# lockdriver.net
KiCad netlist of a schematic drawn in Altium Designer
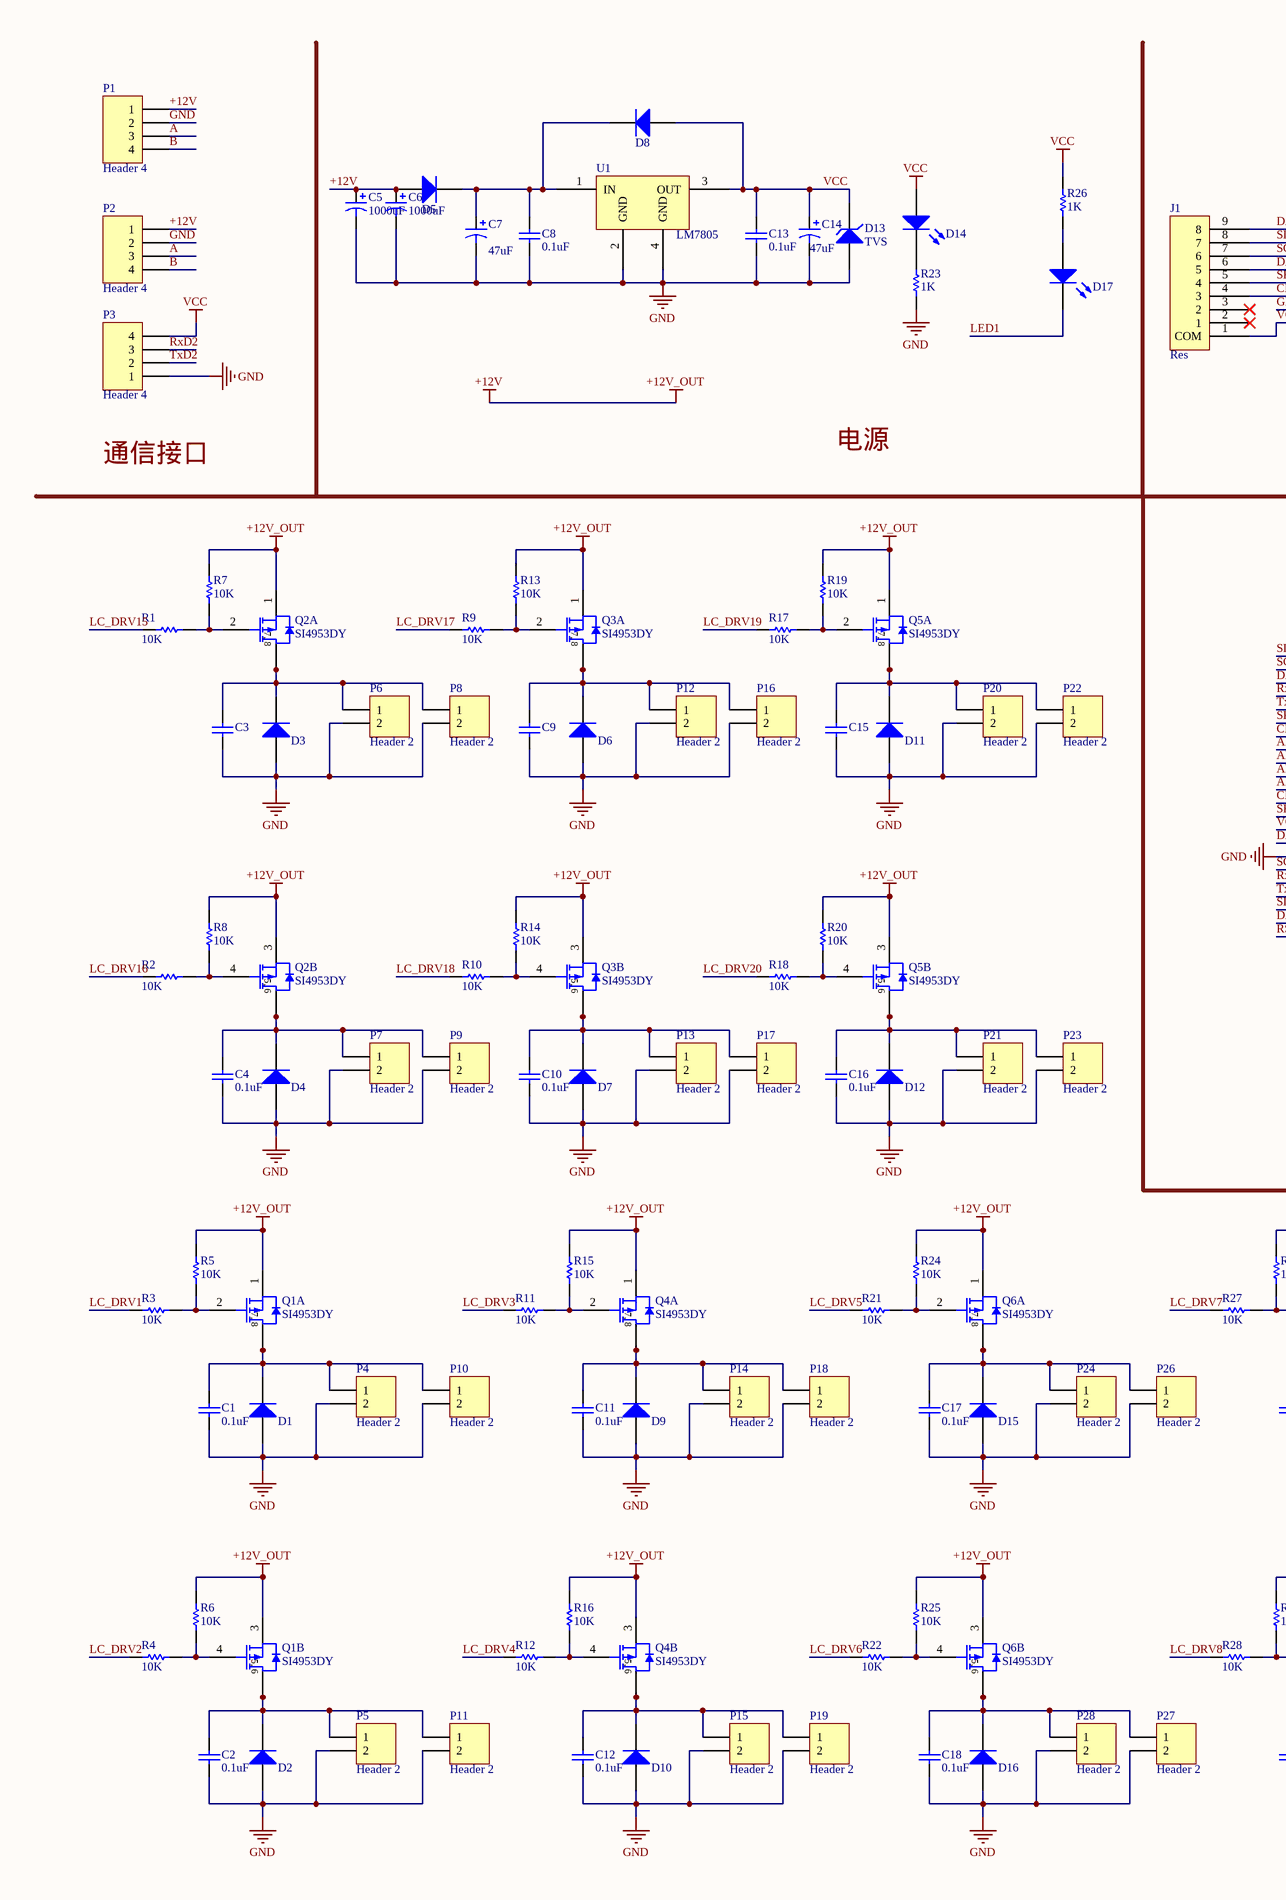
[diagram p0: lockdriver.SchDoc, left]
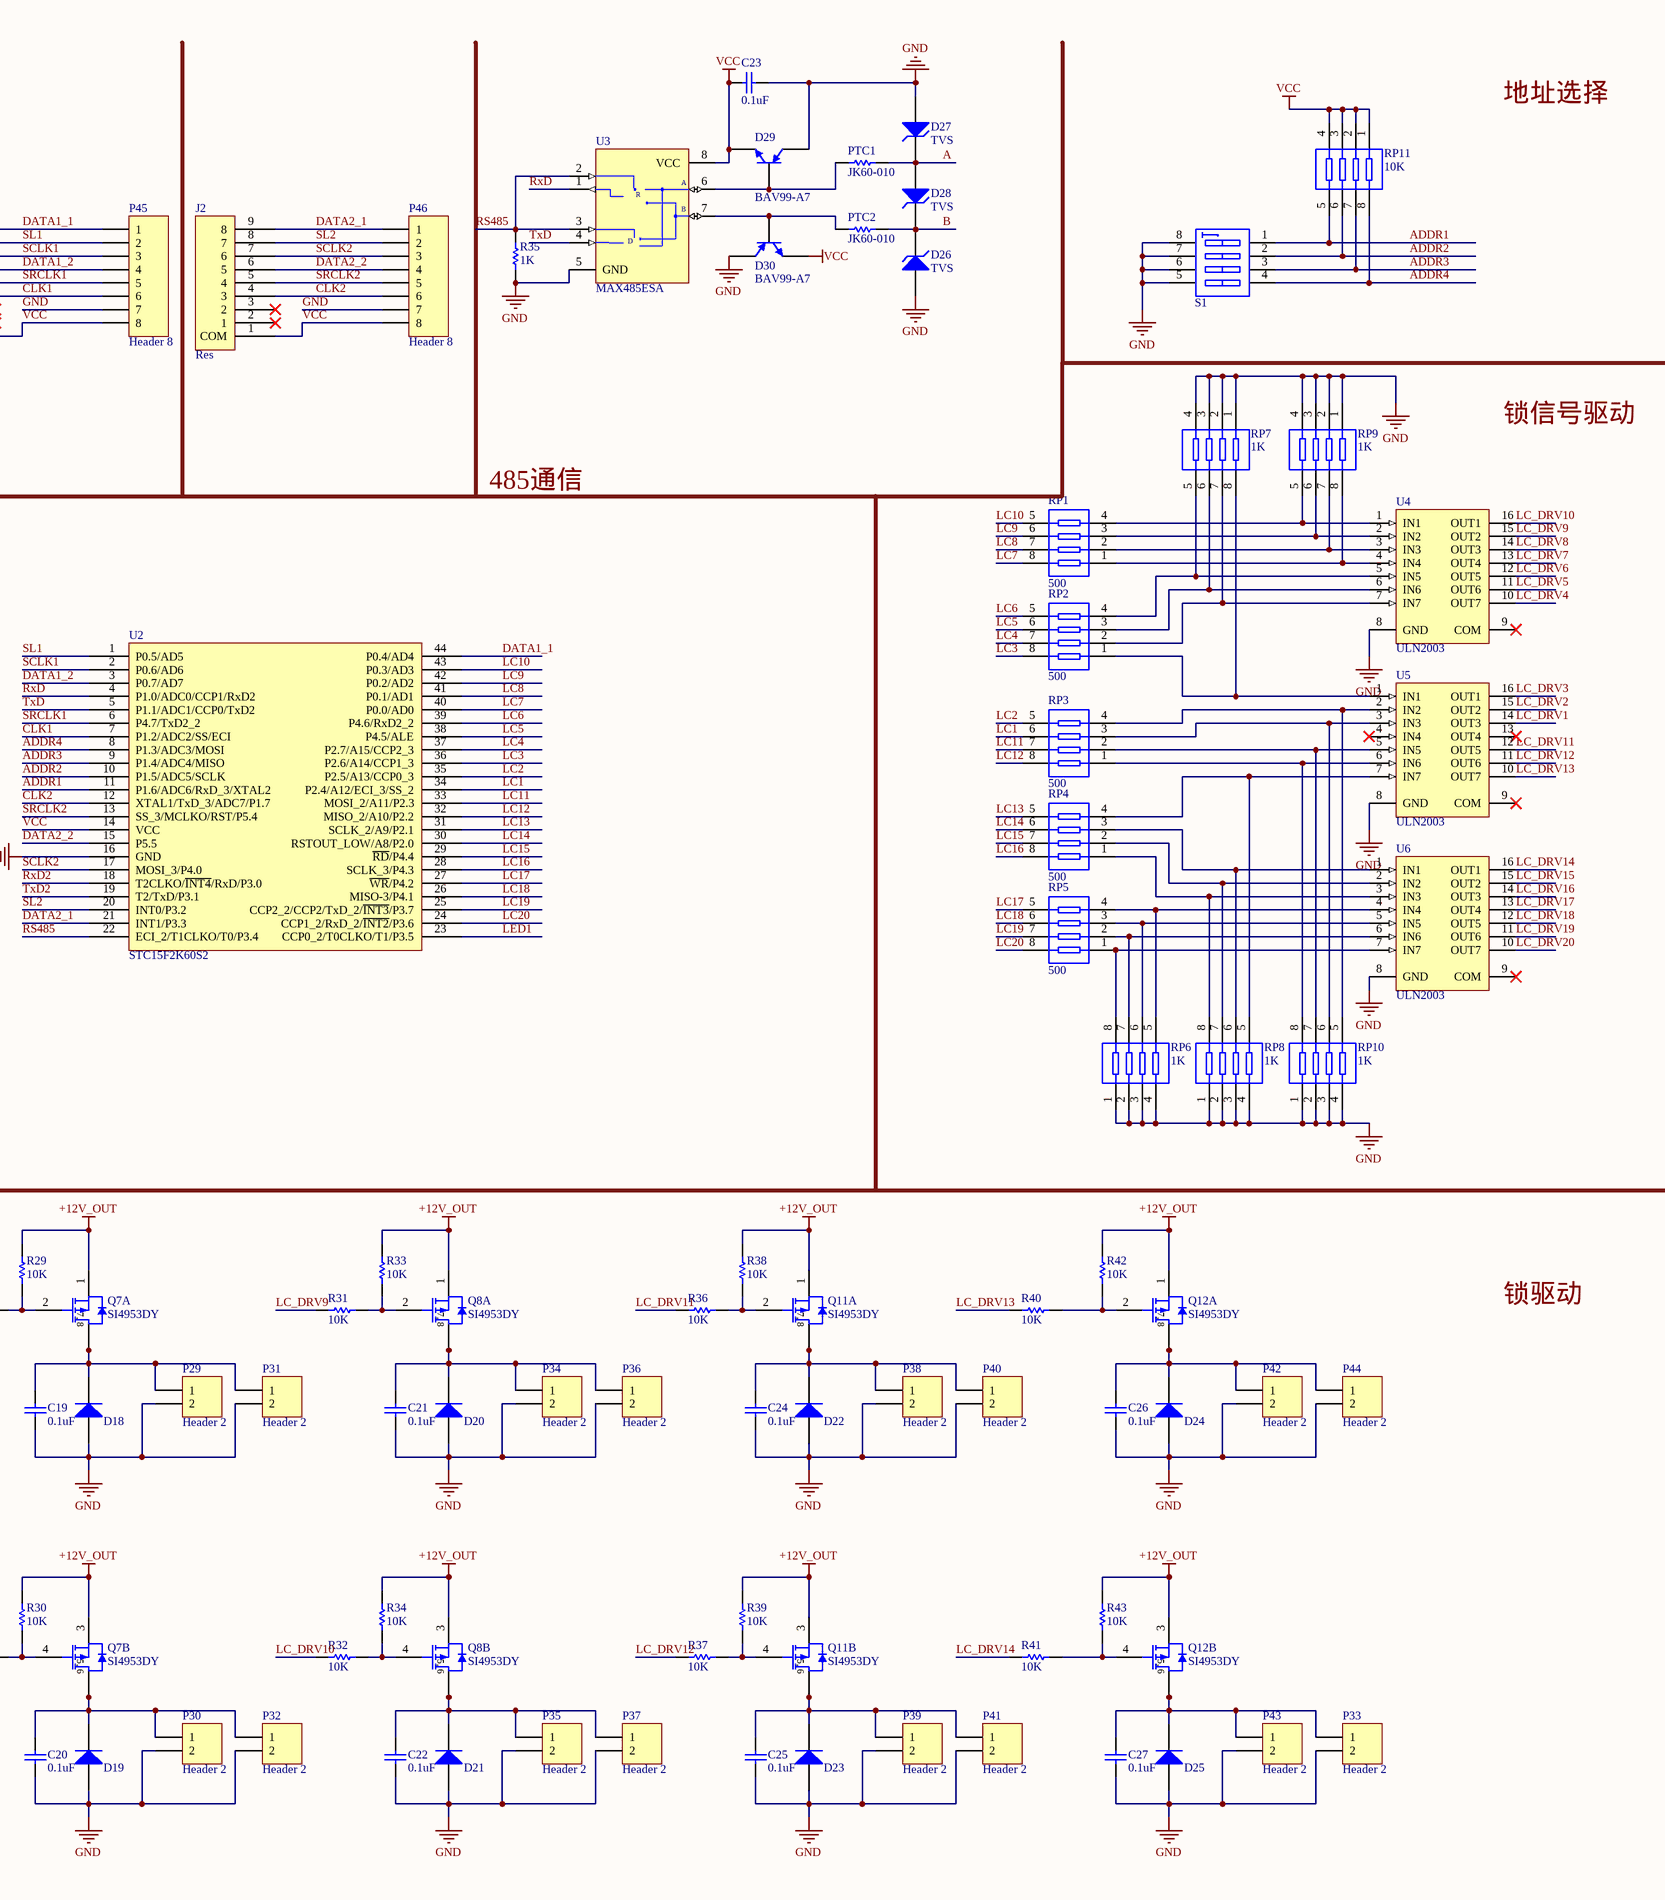
[diagram p1: lockdriver.SchDoc, right]

(export (version "E")
  (design (tool "Eeschema 10.0.6"))
  (components
    (comp (ref "C1")
      (value "0.1uF")
      (footprint "CAPC2012M")
      (description "Capacitor")
      (fields (field (name "PUBLISHER") "Altium Limited"))
      (libsource (lib "device") (part "Cap"))
    )
    (comp (ref "C2")
      (value "0.1uF")
      (footprint "CAPC2012M")
      (description "Capacitor")
      (fields (field (name "PUBLISHER") "Altium Limited"))
      (libsource (lib "device") (part "Cap"))
    )
    (comp (ref "C3")
      (value "0.1uF")
      (footprint "CAPC2012M")
      (description "Capacitor")
      (fields (field (name "PUBLISHER") "Altium Limited"))
      (libsource (lib "device") (part "Cap"))
    )
    (comp (ref "C4")
      (value "0.1uF")
      (footprint "CAPC2012M")
      (description "Capacitor")
      (fields (field (name "PUBLISHER") "Altium Limited"))
      (libsource (lib "device") (part "Cap"))
    )
    (comp (ref "C5")
      (value "1000uF")
      (footprint "CAPPR5-10x12.5")
      (description "Polarized Capacitor (1000uf)")
      (fields (field (name "PUBLISHER") "Altium Limited"))
      (libsource (lib "device") (part "Cap Pol4"))
    )
    (comp (ref "C6")
      (value "1000uF")
      (footprint "CAPPR5-10x12.5")
      (description "Polarized Capacitor (1000uf)")
      (fields (field (name "PUBLISHER") "Altium Limited"))
      (libsource (lib "device") (part "Cap Pol4"))
    )
    (comp (ref "C7")
      (value "47uF")
      (footprint "CAPPR2-5x11.5")
      (description "Polarized Capacitor (22uf-47uf)")
      (fields (field (name "Comment") "Cap Pol2") (field (name "PUBLISHER") "Altium Limited"))
      (libsource (lib "device") (part "Cap Pol2"))
    )
    (comp (ref "C8")
      (value "0.1uF")
      (footprint "CAPC2012M")
      (description "Capacitor")
      (fields (field (name "PUBLISHER") "Altium Limited"))
      (libsource (lib "device") (part "Cap"))
    )
    (comp (ref "C9")
      (value "0.1uF")
      (footprint "CAPC2012M")
      (description "Capacitor")
      (fields (field (name "PUBLISHER") "Altium Limited"))
      (libsource (lib "device") (part "Cap"))
    )
    (comp (ref "C10")
      (value "0.1uF")
      (footprint "CAPC2012M")
      (description "Capacitor")
      (fields (field (name "PUBLISHER") "Altium Limited"))
      (libsource (lib "device") (part "Cap"))
    )
    (comp (ref "C11")
      (value "0.1uF")
      (footprint "CAPC2012M")
      (description "Capacitor")
      (fields (field (name "PUBLISHER") "Altium Limited"))
      (libsource (lib "device") (part "Cap"))
    )
    (comp (ref "C12")
      (value "0.1uF")
      (footprint "CAPC2012M")
      (description "Capacitor")
      (fields (field (name "PUBLISHER") "Altium Limited"))
      (libsource (lib "device") (part "Cap"))
    )
    (comp (ref "C13")
      (value "0.1uF")
      (footprint "CAPC2012M")
      (description "Capacitor")
      (fields (field (name "PUBLISHER") "Altium Limited"))
      (libsource (lib "device") (part "Cap"))
    )
    (comp (ref "C14")
      (value "47uF")
      (footprint "CAPPR2-5x11.5")
      (description "Polarized Capacitor (22uf-47uf)")
      (fields (field (name "Comment") "Cap Pol2") (field (name "PUBLISHER") "Altium Limited"))
      (libsource (lib "device") (part "Cap Pol2"))
    )
    (comp (ref "C15")
      (value "0.1uF")
      (footprint "CAPC2012M")
      (description "Capacitor")
      (fields (field (name "PUBLISHER") "Altium Limited"))
      (libsource (lib "device") (part "Cap"))
    )
    (comp (ref "C16")
      (value "0.1uF")
      (footprint "CAPC2012M")
      (description "Capacitor")
      (fields (field (name "PUBLISHER") "Altium Limited"))
      (libsource (lib "device") (part "Cap"))
    )
    (comp (ref "C17")
      (value "0.1uF")
      (footprint "CAPC2012M")
      (description "Capacitor")
      (fields (field (name "PUBLISHER") "Altium Limited"))
      (libsource (lib "device") (part "Cap"))
    )
    (comp (ref "C18")
      (value "0.1uF")
      (footprint "CAPC2012M")
      (description "Capacitor")
      (fields (field (name "PUBLISHER") "Altium Limited"))
      (libsource (lib "device") (part "Cap"))
    )
    (comp (ref "C19")
      (value "0.1uF")
      (footprint "CAPC2012M")
      (description "Capacitor")
      (fields (field (name "PUBLISHER") "Altium Limited"))
      (libsource (lib "device") (part "Cap"))
    )
    (comp (ref "C20")
      (value "0.1uF")
      (footprint "CAPC2012M")
      (description "Capacitor")
      (fields (field (name "PUBLISHER") "Altium Limited"))
      (libsource (lib "device") (part "Cap"))
    )
    (comp (ref "C21")
      (value "0.1uF")
      (footprint "CAPC2012M")
      (description "Capacitor")
      (fields (field (name "PUBLISHER") "Altium Limited"))
      (libsource (lib "device") (part "Cap"))
    )
    (comp (ref "C22")
      (value "0.1uF")
      (footprint "CAPC2012M")
      (description "Capacitor")
      (fields (field (name "PUBLISHER") "Altium Limited"))
      (libsource (lib "device") (part "Cap"))
    )
    (comp (ref "C23")
      (value "0.1uF")
      (footprint "CAPC2012M")
      (description "Capacitor")
      (fields (field (name "PUBLISHER") "Altium Limited"))
      (libsource (lib "device") (part "Cap"))
    )
    (comp (ref "C24")
      (value "0.1uF")
      (footprint "CAPC2012M")
      (description "Capacitor")
      (fields (field (name "PUBLISHER") "Altium Limited"))
      (libsource (lib "device") (part "Cap"))
    )
    (comp (ref "C25")
      (value "0.1uF")
      (footprint "CAPC2012M")
      (description "Capacitor")
      (fields (field (name "PUBLISHER") "Altium Limited"))
      (libsource (lib "device") (part "Cap"))
    )
    (comp (ref "C26")
      (value "0.1uF")
      (footprint "CAPC2012M")
      (description "Capacitor")
      (fields (field (name "PUBLISHER") "Altium Limited"))
      (libsource (lib "device") (part "Cap"))
    )
    (comp (ref "C27")
      (value "0.1uF")
      (footprint "CAPC2012M")
      (description "Capacitor")
      (fields (field (name "PUBLISHER") "Altium Limited"))
      (libsource (lib "device") (part "Cap"))
    )
    (comp (ref "D1")
      (value "1N4007")
      (footprint "DSO-C2/X1.8")
      (description "Default Diode")
      (fields (field (name "PUBLISHER") "Altium Limited"))
      (libsource (lib "device") (part "Diode"))
    )
    (comp (ref "D2")
      (value "1N4007")
      (footprint "DSO-C2/X1.8")
      (description "Default Diode")
      (fields (field (name "PUBLISHER") "Altium Limited"))
      (libsource (lib "device") (part "Diode"))
    )
    (comp (ref "D3")
      (value "1N4007")
      (footprint "DSO-C2/X1.8")
      (description "Default Diode")
      (fields (field (name "PUBLISHER") "Altium Limited"))
      (libsource (lib "device") (part "Diode"))
    )
    (comp (ref "D4")
      (value "1N4007")
      (footprint "DSO-C2/X1.8")
      (description "Default Diode")
      (fields (field (name "PUBLISHER") "Altium Limited"))
      (libsource (lib "device") (part "Diode"))
    )
    (comp (ref "D5")
      (value "1N4007")
      (footprint "DSO-C2/X1.8")
      (description "Default Diode")
      (fields (field (name "PUBLISHER") "Altium Limited"))
      (libsource (lib "device") (part "Diode"))
    )
    (comp (ref "D6")
      (value "1N4007")
      (footprint "DSO-C2/X1.8")
      (description "Default Diode")
      (fields (field (name "PUBLISHER") "Altium Limited"))
      (libsource (lib "device") (part "Diode"))
    )
    (comp (ref "D7")
      (value "1N4007")
      (footprint "DSO-C2/X1.8")
      (description "Default Diode")
      (fields (field (name "PUBLISHER") "Altium Limited"))
      (libsource (lib "device") (part "Diode"))
    )
    (comp (ref "D8")
      (value "1N4007")
      (footprint "DSO-C2/X1.8")
      (description "Default Diode")
      (fields (field (name "PUBLISHER") "Altium Limited"))
      (libsource (lib "device") (part "Diode"))
    )
    (comp (ref "D9")
      (value "1N4007")
      (footprint "DSO-C2/X1.8")
      (description "Default Diode")
      (fields (field (name "PUBLISHER") "Altium Limited"))
      (libsource (lib "device") (part "Diode"))
    )
    (comp (ref "D10")
      (value "1N4007")
      (footprint "DSO-C2/X1.8")
      (description "Default Diode")
      (fields (field (name "PUBLISHER") "Altium Limited"))
      (libsource (lib "device") (part "Diode"))
    )
    (comp (ref "D11")
      (value "1N4007")
      (footprint "DSO-C2/X1.8")
      (description "Default Diode")
      (fields (field (name "PUBLISHER") "Altium Limited"))
      (libsource (lib "device") (part "Diode"))
    )
    (comp (ref "D12")
      (value "1N4007")
      (footprint "DSO-C2/X1.8")
      (description "Default Diode")
      (fields (field (name "PUBLISHER") "Altium Limited"))
      (libsource (lib "device") (part "Diode"))
    )
    (comp (ref "D13")
      (value "TVS")
      (footprint "DSO-C2/X1.8")
      (description "TVS瞬态抑制二极管")
      (fields (field (name "PUBLISHER") "Altium Limited"))
      (libsource (lib "device") (part "TVS"))
    )
    (comp (ref "D14")
      (value "LED")
      (footprint "LED2012M")
      (description "Typical INFRARED GaAs LED")
      (fields (field (name "PUBLISHER") "Altium Limited"))
      (libsource (lib "device") (part "LED"))
    )
    (comp (ref "D15")
      (value "1N4007")
      (footprint "DSO-C2/X1.8")
      (description "Default Diode")
      (fields (field (name "PUBLISHER") "Altium Limited"))
      (libsource (lib "device") (part "Diode"))
    )
    (comp (ref "D16")
      (value "1N4007")
      (footprint "DSO-C2/X1.8")
      (description "Default Diode")
      (fields (field (name "PUBLISHER") "Altium Limited"))
      (libsource (lib "device") (part "Diode"))
    )
    (comp (ref "D17")
      (value "LED")
      (footprint "LED2012M")
      (description "Typical INFRARED GaAs LED")
      (fields (field (name "PUBLISHER") "Altium Limited"))
      (libsource (lib "device") (part "LED"))
    )
    (comp (ref "D18")
      (value "1N4007")
      (footprint "DSO-C2/X1.8")
      (description "Default Diode")
      (fields (field (name "PUBLISHER") "Altium Limited"))
      (libsource (lib "device") (part "Diode"))
    )
    (comp (ref "D19")
      (value "1N4007")
      (footprint "DSO-C2/X1.8")
      (description "Default Diode")
      (fields (field (name "PUBLISHER") "Altium Limited"))
      (libsource (lib "device") (part "Diode"))
    )
    (comp (ref "D20")
      (value "1N4007")
      (footprint "DSO-C2/X1.8")
      (description "Default Diode")
      (fields (field (name "PUBLISHER") "Altium Limited"))
      (libsource (lib "device") (part "Diode"))
    )
    (comp (ref "D21")
      (value "1N4007")
      (footprint "DSO-C2/X1.8")
      (description "Default Diode")
      (fields (field (name "PUBLISHER") "Altium Limited"))
      (libsource (lib "device") (part "Diode"))
    )
    (comp (ref "D22")
      (value "1N4007")
      (footprint "DSO-C2/X1.8")
      (description "Default Diode")
      (fields (field (name "PUBLISHER") "Altium Limited"))
      (libsource (lib "device") (part "Diode"))
    )
    (comp (ref "D23")
      (value "1N4007")
      (footprint "DSO-C2/X1.8")
      (description "Default Diode")
      (fields (field (name "PUBLISHER") "Altium Limited"))
      (libsource (lib "device") (part "Diode"))
    )
    (comp (ref "D24")
      (value "1N4007")
      (footprint "DSO-C2/X1.8")
      (description "Default Diode")
      (fields (field (name "PUBLISHER") "Altium Limited"))
      (libsource (lib "device") (part "Diode"))
    )
    (comp (ref "D25")
      (value "1N4007")
      (footprint "DSO-C2/X1.8")
      (description "Default Diode")
      (fields (field (name "PUBLISHER") "Altium Limited"))
      (libsource (lib "device") (part "Diode"))
    )
    (comp (ref "D26")
      (value "TVS")
      (footprint "DSO-C2/X1.8")
      (description "TVS瞬态抑制二极管")
      (fields (field (name "PUBLISHER") "Altium Limited"))
      (libsource (lib "device") (part "TVS"))
    )
    (comp (ref "D27")
      (value "TVS")
      (footprint "DSO-C2/X1.8")
      (description "TVS瞬态抑制二极管")
      (fields (field (name "PUBLISHER") "Altium Limited"))
      (libsource (lib "device") (part "TVS"))
    )
    (comp (ref "D28")
      (value "TVS")
      (footprint "DSO-C2/X1.8")
      (description "TVS瞬态抑制二极管")
      (fields (field (name "PUBLISHER") "Altium Limited"))
      (libsource (lib "device") (part "TVS"))
    )
    (comp (ref "D29") (value "BAV99-A7") (footprint "SOT23-3M") (libsource (lib "device") (part "BAV99-A7")))
    (comp (ref "D30") (value "BAV99-A7") (footprint "SOT23-3M") (libsource (lib "device") (part "BAV99-A7")))
    (comp (ref "J1") (value "Res") (footprint "SIP9") (libsource (lib "device") (part "Res Pack2")))
    (comp (ref "J2") (value "Res") (footprint "SIP9") (libsource (lib "device") (part "Res Pack2")))
    (comp (ref "P1")
      (value "Header 4")
      (footprint "VH396-4")
      (description "Header, 4-Pin")
      (fields (field (name "PUBLISHER") "Altium Limited"))
      (libsource (lib "connector") (part "Header 4"))
    )
    (comp (ref "P2")
      (value "Header 4")
      (footprint "VH396-4")
      (description "Header, 4-Pin")
      (fields (field (name "PUBLISHER") "Altium Limited"))
      (libsource (lib "connector") (part "Header 4"))
    )
    (comp (ref "P3")
      (value "Header 4")
      (footprint "HDR1X4")
      (description "Header, 4-Pin")
      (fields (field (name "PUBLISHER") "Altium Limited"))
      (libsource (lib "") (part "Header 4_1"))
    )
    (comp (ref "P4")
      (value "Header 2")
      (footprint "VH396-2")
      (description "Header, 2-Pin")
      (fields (field (name "PUBLISHER") "Altium Limited"))
      (libsource (lib "connector") (part "Header 2"))
    )
    (comp (ref "P5")
      (value "Header 2")
      (footprint "VH396-2")
      (description "Header, 2-Pin")
      (fields (field (name "PUBLISHER") "Altium Limited"))
      (libsource (lib "connector") (part "Header 2"))
    )
    (comp (ref "P6")
      (value "Header 2")
      (footprint "VH396-2")
      (description "Header, 2-Pin")
      (fields (field (name "PUBLISHER") "Altium Limited"))
      (libsource (lib "connector") (part "Header 2"))
    )
    (comp (ref "P7")
      (value "Header 2")
      (footprint "VH396-2")
      (description "Header, 2-Pin")
      (fields (field (name "PUBLISHER") "Altium Limited"))
      (libsource (lib "connector") (part "Header 2"))
    )
    (comp (ref "P8")
      (value "Header 2")
      (footprint "XH254-2")
      (description "Header, 2-Pin")
      (fields (field (name "PUBLISHER") "Altium Limited"))
      (libsource (lib "connector") (part "Header 2"))
    )
    (comp (ref "P9")
      (value "Header 2")
      (footprint "XH254-2")
      (description "Header, 2-Pin")
      (fields (field (name "PUBLISHER") "Altium Limited"))
      (libsource (lib "connector") (part "Header 2"))
    )
    (comp (ref "P10")
      (value "Header 2")
      (footprint "XH254-2")
      (description "Header, 2-Pin")
      (fields (field (name "PUBLISHER") "Altium Limited"))
      (libsource (lib "connector") (part "Header 2"))
    )
    (comp (ref "P11")
      (value "Header 2")
      (footprint "XH254-2")
      (description "Header, 2-Pin")
      (fields (field (name "PUBLISHER") "Altium Limited"))
      (libsource (lib "connector") (part "Header 2"))
    )
    (comp (ref "P12")
      (value "Header 2")
      (footprint "VH396-2")
      (description "Header, 2-Pin")
      (fields (field (name "PUBLISHER") "Altium Limited"))
      (libsource (lib "connector") (part "Header 2"))
    )
    (comp (ref "P13")
      (value "Header 2")
      (footprint "VH396-2")
      (description "Header, 2-Pin")
      (fields (field (name "PUBLISHER") "Altium Limited"))
      (libsource (lib "connector") (part "Header 2"))
    )
    (comp (ref "P14")
      (value "Header 2")
      (footprint "VH396-2")
      (description "Header, 2-Pin")
      (fields (field (name "PUBLISHER") "Altium Limited"))
      (libsource (lib "connector") (part "Header 2"))
    )
    (comp (ref "P15")
      (value "Header 2")
      (footprint "VH396-2")
      (description "Header, 2-Pin")
      (fields (field (name "PUBLISHER") "Altium Limited"))
      (libsource (lib "connector") (part "Header 2"))
    )
    (comp (ref "P16")
      (value "Header 2")
      (footprint "XH254-2")
      (description "Header, 2-Pin")
      (fields (field (name "PUBLISHER") "Altium Limited"))
      (libsource (lib "connector") (part "Header 2"))
    )
    (comp (ref "P17")
      (value "Header 2")
      (footprint "XH254-2")
      (description "Header, 2-Pin")
      (fields (field (name "PUBLISHER") "Altium Limited"))
      (libsource (lib "connector") (part "Header 2"))
    )
    (comp (ref "P18")
      (value "Header 2")
      (footprint "XH254-2")
      (description "Header, 2-Pin")
      (fields (field (name "PUBLISHER") "Altium Limited"))
      (libsource (lib "connector") (part "Header 2"))
    )
    (comp (ref "P19")
      (value "Header 2")
      (footprint "XH254-2")
      (description "Header, 2-Pin")
      (fields (field (name "PUBLISHER") "Altium Limited"))
      (libsource (lib "connector") (part "Header 2"))
    )
    (comp (ref "P20")
      (value "Header 2")
      (footprint "VH396-2")
      (description "Header, 2-Pin")
      (fields (field (name "PUBLISHER") "Altium Limited"))
      (libsource (lib "connector") (part "Header 2"))
    )
    (comp (ref "P21")
      (value "Header 2")
      (footprint "VH396-2")
      (description "Header, 2-Pin")
      (fields (field (name "PUBLISHER") "Altium Limited"))
      (libsource (lib "connector") (part "Header 2"))
    )
    (comp (ref "P22")
      (value "Header 2")
      (footprint "XH254-2")
      (description "Header, 2-Pin")
      (fields (field (name "PUBLISHER") "Altium Limited"))
      (libsource (lib "connector") (part "Header 2"))
    )
    (comp (ref "P23")
      (value "Header 2")
      (footprint "XH254-2")
      (description "Header, 2-Pin")
      (fields (field (name "PUBLISHER") "Altium Limited"))
      (libsource (lib "connector") (part "Header 2"))
    )
    (comp (ref "P24")
      (value "Header 2")
      (footprint "VH396-2")
      (description "Header, 2-Pin")
      (fields (field (name "PUBLISHER") "Altium Limited"))
      (libsource (lib "connector") (part "Header 2"))
    )
    (comp (ref "P26")
      (value "Header 2")
      (footprint "XH254-2")
      (description "Header, 2-Pin")
      (fields (field (name "PUBLISHER") "Altium Limited"))
      (libsource (lib "connector") (part "Header 2"))
    )
    (comp (ref "P27")
      (value "Header 2")
      (footprint "XH254-2")
      (description "Header, 2-Pin")
      (fields (field (name "PUBLISHER") "Altium Limited"))
      (libsource (lib "connector") (part "Header 2"))
    )
    (comp (ref "P28")
      (value "Header 2")
      (footprint "VH396-2")
      (description "Header, 2-Pin")
      (fields (field (name "PUBLISHER") "Altium Limited"))
      (libsource (lib "connector") (part "Header 2"))
    )
    (comp (ref "P29")
      (value "Header 2")
      (footprint "VH396-2")
      (description "Header, 2-Pin")
      (fields (field (name "PUBLISHER") "Altium Limited"))
      (libsource (lib "connector") (part "Header 2"))
    )
    (comp (ref "P30")
      (value "Header 2")
      (footprint "VH396-2")
      (description "Header, 2-Pin")
      (fields (field (name "PUBLISHER") "Altium Limited"))
      (libsource (lib "connector") (part "Header 2"))
    )
    (comp (ref "P31")
      (value "Header 2")
      (footprint "XH254-2")
      (description "Header, 2-Pin")
      (fields (field (name "PUBLISHER") "Altium Limited"))
      (libsource (lib "connector") (part "Header 2"))
    )
    (comp (ref "P32")
      (value "Header 2")
      (footprint "XH254-2")
      (description "Header, 2-Pin")
      (fields (field (name "PUBLISHER") "Altium Limited"))
      (libsource (lib "connector") (part "Header 2"))
    )
    (comp (ref "P33")
      (value "Header 2")
      (footprint "XH254-2")
      (description "Header, 2-Pin")
      (fields (field (name "PUBLISHER") "Altium Limited"))
      (libsource (lib "connector") (part "Header 2"))
    )
    (comp (ref "P34")
      (value "Header 2")
      (footprint "VH396-2")
      (description "Header, 2-Pin")
      (fields (field (name "PUBLISHER") "Altium Limited"))
      (libsource (lib "connector") (part "Header 2"))
    )
    (comp (ref "P35")
      (value "Header 2")
      (footprint "VH396-2")
      (description "Header, 2-Pin")
      (fields (field (name "PUBLISHER") "Altium Limited"))
      (libsource (lib "connector") (part "Header 2"))
    )
    (comp (ref "P36")
      (value "Header 2")
      (footprint "XH254-2")
      (description "Header, 2-Pin")
      (fields (field (name "PUBLISHER") "Altium Limited"))
      (libsource (lib "connector") (part "Header 2"))
    )
    (comp (ref "P37")
      (value "Header 2")
      (footprint "XH254-2")
      (description "Header, 2-Pin")
      (fields (field (name "PUBLISHER") "Altium Limited"))
      (libsource (lib "connector") (part "Header 2"))
    )
    (comp (ref "P38")
      (value "Header 2")
      (footprint "VH396-2")
      (description "Header, 2-Pin")
      (fields (field (name "PUBLISHER") "Altium Limited"))
      (libsource (lib "connector") (part "Header 2"))
    )
    (comp (ref "P39")
      (value "Header 2")
      (footprint "VH396-2")
      (description "Header, 2-Pin")
      (fields (field (name "PUBLISHER") "Altium Limited"))
      (libsource (lib "connector") (part "Header 2"))
    )
    (comp (ref "P40")
      (value "Header 2")
      (footprint "XH254-2")
      (description "Header, 2-Pin")
      (fields (field (name "PUBLISHER") "Altium Limited"))
      (libsource (lib "connector") (part "Header 2"))
    )
    (comp (ref "P41")
      (value "Header 2")
      (footprint "XH254-2")
      (description "Header, 2-Pin")
      (fields (field (name "PUBLISHER") "Altium Limited"))
      (libsource (lib "connector") (part "Header 2"))
    )
    (comp (ref "P42")
      (value "Header 2")
      (footprint "VH396-2")
      (description "Header, 2-Pin")
      (fields (field (name "PUBLISHER") "Altium Limited"))
      (libsource (lib "connector") (part "Header 2"))
    )
    (comp (ref "P43")
      (value "Header 2")
      (footprint "VH396-2")
      (description "Header, 2-Pin")
      (fields (field (name "PUBLISHER") "Altium Limited"))
      (libsource (lib "connector") (part "Header 2"))
    )
    (comp (ref "P44")
      (value "Header 2")
      (footprint "XH254-2")
      (description "Header, 2-Pin")
      (fields (field (name "PUBLISHER") "Altium Limited"))
      (libsource (lib "connector") (part "Header 2"))
    )
    (comp (ref "P45")
      (value "Header 8")
      (footprint "XH254-8")
      (description "Header, 8-Pin")
      (fields (field (name "PUBLISHER") "Altium Limited"))
      (libsource (lib "connector") (part "Header 8"))
    )
    (comp (ref "P46")
      (value "Header 8")
      (footprint "XH254-8")
      (description "Header, 8-Pin")
      (fields (field (name "PUBLISHER") "Altium Limited"))
      (libsource (lib "connector") (part "Header 8"))
    )
    (comp (ref "PTC1")
      (value "JK60-010")
      (footprint "RESC2012M")
      (description "Resistor")
      (fields (field (name "PUBLISHER") "Altium Limited"))
      (libsource (lib "device") (part "Res"))
    )
    (comp (ref "PTC2")
      (value "JK60-010")
      (footprint "RESC2012M")
      (description "Resistor")
      (fields (field (name "PUBLISHER") "Altium Limited"))
      (libsource (lib "device") (part "Res"))
    )
    (comp (ref "Q1")
      (value "SI4953DY")
      (footprint "SO8_M")
      (description "Dual P-Channel 30V (D-S) Rated  MOSFET")
      (fields (field (name "PUBLISHER") "Altium Limited"))
      (libsource (lib "ic") (part "SI4953DY"))
    )
    (comp (ref "Q2")
      (value "SI4953DY")
      (footprint "SO8_M")
      (description "Dual P-Channel 30V (D-S) Rated  MOSFET")
      (fields (field (name "PUBLISHER") "Altium Limited"))
      (libsource (lib "ic") (part "SI4953DY"))
    )
    (comp (ref "Q3")
      (value "SI4953DY")
      (footprint "SO8_M")
      (description "Dual P-Channel 30V (D-S) Rated  MOSFET")
      (fields (field (name "PUBLISHER") "Altium Limited"))
      (libsource (lib "ic") (part "SI4953DY"))
    )
    (comp (ref "Q4")
      (value "SI4953DY")
      (footprint "SO8_M")
      (description "Dual P-Channel 30V (D-S) Rated  MOSFET")
      (fields (field (name "PUBLISHER") "Altium Limited"))
      (libsource (lib "ic") (part "SI4953DY"))
    )
    (comp (ref "Q5")
      (value "SI4953DY")
      (footprint "SO8_M")
      (description "Dual P-Channel 30V (D-S) Rated  MOSFET")
      (fields (field (name "PUBLISHER") "Altium Limited"))
      (libsource (lib "ic") (part "SI4953DY"))
    )
    (comp (ref "Q6")
      (value "SI4953DY")
      (footprint "SO8_M")
      (description "Dual P-Channel 30V (D-S) Rated  MOSFET")
      (fields (field (name "PUBLISHER") "Altium Limited"))
      (libsource (lib "ic") (part "SI4953DY"))
    )
    (comp (ref "Q7")
      (value "SI4953DY")
      (footprint "SO8_M")
      (description "Dual P-Channel 30V (D-S) Rated  MOSFET")
      (fields (field (name "PUBLISHER") "Altium Limited"))
      (libsource (lib "ic") (part "SI4953DY"))
    )
    (comp (ref "Q8")
      (value "SI4953DY")
      (footprint "SO8_M")
      (description "Dual P-Channel 30V (D-S) Rated  MOSFET")
      (fields (field (name "PUBLISHER") "Altium Limited"))
      (libsource (lib "ic") (part "SI4953DY"))
    )
    (comp (ref "Q11")
      (value "SI4953DY")
      (footprint "SO8_M")
      (description "Dual P-Channel 30V (D-S) Rated  MOSFET")
      (fields (field (name "PUBLISHER") "Altium Limited"))
      (libsource (lib "ic") (part "SI4953DY"))
    )
    (comp (ref "Q12")
      (value "SI4953DY")
      (footprint "SO8_M")
      (description "Dual P-Channel 30V (D-S) Rated  MOSFET")
      (fields (field (name "PUBLISHER") "Altium Limited"))
      (libsource (lib "ic") (part "SI4953DY"))
    )
    (comp (ref "R1")
      (value "10K")
      (footprint "RESC2012M")
      (description "Resistor")
      (fields (field (name "PUBLISHER") "Altium Limited"))
      (libsource (lib "device") (part "Res"))
    )
    (comp (ref "R2")
      (value "10K")
      (footprint "RESC2012M")
      (description "Resistor")
      (fields (field (name "PUBLISHER") "Altium Limited"))
      (libsource (lib "device") (part "Res"))
    )
    (comp (ref "R3")
      (value "10K")
      (footprint "RESC2012M")
      (description "Resistor")
      (fields (field (name "PUBLISHER") "Altium Limited"))
      (libsource (lib "device") (part "Res"))
    )
    (comp (ref "R4")
      (value "10K")
      (footprint "RESC2012M")
      (description "Resistor")
      (fields (field (name "PUBLISHER") "Altium Limited"))
      (libsource (lib "device") (part "Res"))
    )
    (comp (ref "R5")
      (value "10K")
      (footprint "RESC2012M")
      (description "Resistor")
      (fields (field (name "PUBLISHER") "Altium Limited"))
      (libsource (lib "device") (part "Res"))
    )
    (comp (ref "R6")
      (value "10K")
      (footprint "RESC2012M")
      (description "Resistor")
      (fields (field (name "PUBLISHER") "Altium Limited"))
      (libsource (lib "device") (part "Res"))
    )
    (comp (ref "R7")
      (value "10K")
      (footprint "RESC2012M")
      (description "Resistor")
      (fields (field (name "PUBLISHER") "Altium Limited"))
      (libsource (lib "device") (part "Res"))
    )
    (comp (ref "R8")
      (value "10K")
      (footprint "RESC2012M")
      (description "Resistor")
      (fields (field (name "PUBLISHER") "Altium Limited"))
      (libsource (lib "device") (part "Res"))
    )
    (comp (ref "R9")
      (value "10K")
      (footprint "RESC2012M")
      (description "Resistor")
      (fields (field (name "PUBLISHER") "Altium Limited"))
      (libsource (lib "device") (part "Res"))
    )
    (comp (ref "R10")
      (value "10K")
      (footprint "RESC2012M")
      (description "Resistor")
      (fields (field (name "PUBLISHER") "Altium Limited"))
      (libsource (lib "device") (part "Res"))
    )
    (comp (ref "R11")
      (value "10K")
      (footprint "RESC2012M")
      (description "Resistor")
      (fields (field (name "PUBLISHER") "Altium Limited"))
      (libsource (lib "device") (part "Res"))
    )
    (comp (ref "R12")
      (value "10K")
      (footprint "RESC2012M")
      (description "Resistor")
      (fields (field (name "PUBLISHER") "Altium Limited"))
      (libsource (lib "device") (part "Res"))
    )
    (comp (ref "R13")
      (value "10K")
      (footprint "RESC2012M")
      (description "Resistor")
      (fields (field (name "PUBLISHER") "Altium Limited"))
      (libsource (lib "device") (part "Res"))
    )
    (comp (ref "R14")
      (value "10K")
      (footprint "RESC2012M")
      (description "Resistor")
      (fields (field (name "PUBLISHER") "Altium Limited"))
      (libsource (lib "device") (part "Res"))
    )
    (comp (ref "R15")
      (value "10K")
      (footprint "RESC2012M")
      (description "Resistor")
      (fields (field (name "PUBLISHER") "Altium Limited"))
      (libsource (lib "device") (part "Res"))
    )
    (comp (ref "R16")
      (value "10K")
      (footprint "RESC2012M")
      (description "Resistor")
      (fields (field (name "PUBLISHER") "Altium Limited"))
      (libsource (lib "device") (part "Res"))
    )
    (comp (ref "R17")
      (value "10K")
      (footprint "RESC2012M")
      (description "Resistor")
      (fields (field (name "PUBLISHER") "Altium Limited"))
      (libsource (lib "device") (part "Res"))
    )
    (comp (ref "R18")
      (value "10K")
      (footprint "RESC2012M")
      (description "Resistor")
      (fields (field (name "PUBLISHER") "Altium Limited"))
      (libsource (lib "device") (part "Res"))
    )
    (comp (ref "R19")
      (value "10K")
      (footprint "RESC2012M")
      (description "Resistor")
      (fields (field (name "PUBLISHER") "Altium Limited"))
      (libsource (lib "device") (part "Res"))
    )
    (comp (ref "R20")
      (value "10K")
      (footprint "RESC2012M")
      (description "Resistor")
      (fields (field (name "PUBLISHER") "Altium Limited"))
      (libsource (lib "device") (part "Res"))
    )
    (comp (ref "R21")
      (value "10K")
      (footprint "RESC2012M")
      (description "Resistor")
      (fields (field (name "PUBLISHER") "Altium Limited"))
      (libsource (lib "device") (part "Res"))
    )
    (comp (ref "R22")
      (value "10K")
      (footprint "RESC2012M")
      (description "Resistor")
      (fields (field (name "PUBLISHER") "Altium Limited"))
      (libsource (lib "device") (part "Res"))
    )
    (comp (ref "R23")
      (value "1K")
      (footprint "RESC2012M")
      (description "Resistor")
      (fields (field (name "PUBLISHER") "Altium Limited"))
      (libsource (lib "device") (part "Res"))
    )
    (comp (ref "R24")
      (value "10K")
      (footprint "RESC2012M")
      (description "Resistor")
      (fields (field (name "PUBLISHER") "Altium Limited"))
      (libsource (lib "device") (part "Res"))
    )
    (comp (ref "R25")
      (value "10K")
      (footprint "RESC2012M")
      (description "Resistor")
      (fields (field (name "PUBLISHER") "Altium Limited"))
      (libsource (lib "device") (part "Res"))
    )
    (comp (ref "R26")
      (value "1K")
      (footprint "RESC2012M")
      (description "Resistor")
      (fields (field (name "PUBLISHER") "Altium Limited"))
      (libsource (lib "device") (part "Res"))
    )
    (comp (ref "R27")
      (value "10K")
      (footprint "RESC2012M")
      (description "Resistor")
      (fields (field (name "PUBLISHER") "Altium Limited"))
      (libsource (lib "device") (part "Res"))
    )
    (comp (ref "R28")
      (value "10K")
      (footprint "RESC2012M")
      (description "Resistor")
      (fields (field (name "PUBLISHER") "Altium Limited"))
      (libsource (lib "device") (part "Res"))
    )
    (comp (ref "R29")
      (value "10K")
      (footprint "RESC2012M")
      (description "Resistor")
      (fields (field (name "PUBLISHER") "Altium Limited"))
      (libsource (lib "device") (part "Res"))
    )
    (comp (ref "R30")
      (value "10K")
      (footprint "RESC2012M")
      (description "Resistor")
      (fields (field (name "PUBLISHER") "Altium Limited"))
      (libsource (lib "device") (part "Res"))
    )
    (comp (ref "R31")
      (value "10K")
      (footprint "RESC2012M")
      (description "Resistor")
      (fields (field (name "PUBLISHER") "Altium Limited"))
      (libsource (lib "device") (part "Res"))
    )
    (comp (ref "R32")
      (value "10K")
      (footprint "RESC2012M")
      (description "Resistor")
      (fields (field (name "PUBLISHER") "Altium Limited"))
      (libsource (lib "device") (part "Res"))
    )
    (comp (ref "R33")
      (value "10K")
      (footprint "RESC2012M")
      (description "Resistor")
      (fields (field (name "PUBLISHER") "Altium Limited"))
      (libsource (lib "device") (part "Res"))
    )
    (comp (ref "R34")
      (value "10K")
      (footprint "RESC2012M")
      (description "Resistor")
      (fields (field (name "PUBLISHER") "Altium Limited"))
      (libsource (lib "device") (part "Res"))
    )
    (comp (ref "R35")
      (value "1K")
      (footprint "RESC2012M")
      (description "Resistor")
      (fields (field (name "PUBLISHER") "Altium Limited"))
      (libsource (lib "device") (part "Res"))
    )
    (comp (ref "R36")
      (value "10K")
      (footprint "RESC2012M")
      (description "Resistor")
      (fields (field (name "PUBLISHER") "Altium Limited"))
      (libsource (lib "device") (part "Res"))
    )
    (comp (ref "R37")
      (value "10K")
      (footprint "RESC2012M")
      (description "Resistor")
      (fields (field (name "PUBLISHER") "Altium Limited"))
      (libsource (lib "device") (part "Res"))
    )
    (comp (ref "R38")
      (value "10K")
      (footprint "RESC2012M")
      (description "Resistor")
      (fields (field (name "PUBLISHER") "Altium Limited"))
      (libsource (lib "device") (part "Res"))
    )
    (comp (ref "R39")
      (value "10K")
      (footprint "RESC2012M")
      (description "Resistor")
      (fields (field (name "PUBLISHER") "Altium Limited"))
      (libsource (lib "device") (part "Res"))
    )
    (comp (ref "R40")
      (value "10K")
      (footprint "RESC2012M")
      (description "Resistor")
      (fields (field (name "PUBLISHER") "Altium Limited"))
      (libsource (lib "device") (part "Res"))
    )
    (comp (ref "R41")
      (value "10K")
      (footprint "RESC2012M")
      (description "Resistor")
      (fields (field (name "PUBLISHER") "Altium Limited"))
      (libsource (lib "device") (part "Res"))
    )
    (comp (ref "R42")
      (value "10K")
      (footprint "RESC2012M")
      (description "Resistor")
      (fields (field (name "PUBLISHER") "Altium Limited"))
      (libsource (lib "device") (part "Res"))
    )
    (comp (ref "R43")
      (value "10K")
      (footprint "RESC2012M")
      (description "Resistor")
      (fields (field (name "PUBLISHER") "Altium Limited"))
      (libsource (lib "device") (part "Res"))
    )
    (comp (ref "RP1") (value "500") (footprint "EXB38V") (libsource (lib "device") (part "Res Pack")))
    (comp (ref "RP2") (value "500") (footprint "EXB38V") (libsource (lib "device") (part "Res Pack")))
    (comp (ref "RP3") (value "500") (footprint "EXB38V") (libsource (lib "device") (part "Res Pack")))
    (comp (ref "RP4") (value "500") (footprint "EXB38V") (libsource (lib "device") (part "Res Pack")))
    (comp (ref "RP5") (value "500") (footprint "EXB38V") (libsource (lib "device") (part "Res Pack")))
    (comp (ref "RP6") (value "1K") (footprint "EXB38V") (libsource (lib "device") (part "Res Pack")))
    (comp (ref "RP7") (value "1K") (footprint "EXB38V") (libsource (lib "device") (part "Res Pack")))
    (comp (ref "RP8") (value "1K") (footprint "EXB38V") (libsource (lib "device") (part "Res Pack")))
    (comp (ref "RP9") (value "1K") (footprint "EXB38V") (libsource (lib "device") (part "Res Pack")))
    (comp (ref "RP10") (value "1K") (footprint "EXB38V") (libsource (lib "device") (part "Res Pack")))
    (comp (ref "RP11") (value "10K") (footprint "EXB38V") (libsource (lib "device") (part "Res Pack")))
    (comp (ref "S1")
      (value "SW DIP-4")
      (footprint "SWITCH-8")
      (description "DIP Switch, 4 Position, SPST")
      (fields (field (name "PUBLISHER") "Altium Limited"))
      (libsource (lib "device") (part "SW DIP-4"))
    )
    (comp (ref "U1") (value "LM7805") (footprint "SOT223-4M") (libsource (lib "ic") (part "LM7805")))
    (comp (ref "U2")
      (value "STC15F2K60S2")
      (footprint "LQFP-44")
      (description "LQFP44")
      (libsource (lib "ic") (part "STC15F2K60S2"))
    )
    (comp (ref "U3")
      (value "MAX485ESA")
      (footprint "SO8_M")
      (description "Low-Power, Slew-Rate-Limited RS-485/RS-422 Transceiver")
      (fields (field (name "PUBLISHER") "Altium Limited"))
      (libsource (lib "ic") (part "MAX485ESA"))
    )
    (comp (ref "U4")
      (value "ULN2003")
      (footprint "SO16_M")
      (description "Seven Darlington Array")
      (fields (field (name "PUBLISHER") "Altium Limited"))
      (libsource (lib "ic") (part "ULN2003"))
    )
    (comp (ref "U5")
      (value "ULN2003")
      (footprint "SO16_M")
      (description "Seven Darlington Array")
      (fields (field (name "PUBLISHER") "Altium Limited"))
      (libsource (lib "ic") (part "ULN2003"))
    )
    (comp (ref "U6")
      (value "ULN2003")
      (footprint "SO16_M")
      (description "Seven Darlington Array")
      (fields (field (name "PUBLISHER") "Altium Limited"))
      (libsource (lib "ic") (part "ULN2003"))
    )
  )
  (nets
    (net (code "1") (name "+12V") (class "Default")
      (node (ref "C5") (pin "1") (pinfunction "1_1") (pintype "passive"))
      (node (ref "C6") (pin "1") (pinfunction "1_1") (pintype "passive"))
      (node (ref "D5") (pin "1") (pinfunction "A_1") (pintype "passive"))
      (node (ref "P1") (pin "1") (pinfunction "1_1") (pintype "passive"))
      (node (ref "P2") (pin "1") (pinfunction "1_1") (pintype "passive"))
      (node (ref "Q1") (pin "1") (pinfunction "S_1") (pintype "passive"))
      (node (ref "Q1") (pin "3") (pinfunction "S_3") (pintype "passive"))
      (node (ref "Q11") (pin "1") (pinfunction "S_1") (pintype "passive"))
      (node (ref "Q11") (pin "3") (pinfunction "S_3") (pintype "passive"))
      (node (ref "Q12") (pin "1") (pinfunction "S_1") (pintype "passive"))
      (node (ref "Q12") (pin "3") (pinfunction "S_3") (pintype "passive"))
      (node (ref "Q2") (pin "1") (pinfunction "S_1") (pintype "passive"))
      (node (ref "Q2") (pin "3") (pinfunction "S_3") (pintype "passive"))
      (node (ref "Q3") (pin "1") (pinfunction "S_1") (pintype "passive"))
      (node (ref "Q3") (pin "3") (pinfunction "S_3") (pintype "passive"))
      (node (ref "Q4") (pin "1") (pinfunction "S_1") (pintype "passive"))
      (node (ref "Q4") (pin "3") (pinfunction "S_3") (pintype "passive"))
      (node (ref "Q5") (pin "1") (pinfunction "S_1") (pintype "passive"))
      (node (ref "Q5") (pin "3") (pinfunction "S_3") (pintype "passive"))
      (node (ref "Q6") (pin "1") (pinfunction "S_1") (pintype "passive"))
      (node (ref "Q6") (pin "3") (pinfunction "S_3") (pintype "passive"))
      (node (ref "Q7") (pin "1") (pinfunction "S_1") (pintype "passive"))
      (node (ref "Q7") (pin "3") (pinfunction "S_3") (pintype "passive"))
      (node (ref "Q8") (pin "1") (pinfunction "S_1") (pintype "passive"))
      (node (ref "Q8") (pin "3") (pinfunction "S_3") (pintype "passive"))
      (node (ref "R13") (pin "2") (pinfunction "2_2") (pintype "passive"))
      (node (ref "R14") (pin "2") (pinfunction "2_2") (pintype "passive"))
      (node (ref "R15") (pin "2") (pinfunction "2_2") (pintype "passive"))
      (node (ref "R16") (pin "2") (pinfunction "2_2") (pintype "passive"))
      (node (ref "R19") (pin "2") (pinfunction "2_2") (pintype "passive"))
      (node (ref "R20") (pin "2") (pinfunction "2_2") (pintype "passive"))
      (node (ref "R24") (pin "2") (pinfunction "2_2") (pintype "passive"))
      (node (ref "R25") (pin "2") (pinfunction "2_2") (pintype "passive"))
      (node (ref "R29") (pin "2") (pinfunction "2_2") (pintype "passive"))
      (node (ref "R30") (pin "2") (pinfunction "2_2") (pintype "passive"))
      (node (ref "R33") (pin "2") (pinfunction "2_2") (pintype "passive"))
      (node (ref "R34") (pin "2") (pinfunction "2_2") (pintype "passive"))
      (node (ref "R38") (pin "2") (pinfunction "2_2") (pintype "passive"))
      (node (ref "R39") (pin "2") (pinfunction "2_2") (pintype "passive"))
      (node (ref "R42") (pin "2") (pinfunction "2_2") (pintype "passive"))
      (node (ref "R43") (pin "2") (pinfunction "2_2") (pintype "passive"))
      (node (ref "R5") (pin "2") (pinfunction "2_2") (pintype "passive"))
      (node (ref "R6") (pin "2") (pinfunction "2_2") (pintype "passive"))
      (node (ref "R7") (pin "2") (pinfunction "2_2") (pintype "passive"))
      (node (ref "R8") (pin "2") (pinfunction "2_2") (pintype "passive"))
    )
    (net (code "2") (name "/A") (class "Default")
      (node (ref "D27") (pin "2") (pinfunction "K_2") (pintype "passive"))
      (node (ref "D28") (pin "1") (pinfunction "A_1") (pintype "passive"))
      (node (ref "P1") (pin "3") (pinfunction "3_3") (pintype "passive"))
      (node (ref "P2") (pin "3") (pinfunction "3_3") (pintype "passive"))
      (node (ref "PTC1") (pin "2") (pinfunction "2_2") (pintype "passive"))
    )
    (net (code "3") (name "/ADDR1") (class "Default")
      (node (ref "RP11") (pin "5") (pinfunction "5_5") (pintype "passive"))
      (node (ref "S1") (pin "1") (pinfunction "A1_1") (pintype "passive"))
      (node (ref "U2") (pin "11") (pinfunction "P1.6/ADC6/RxD_3/XTAL2_11") (pintype "passive"))
    )
    (net (code "4") (name "/ADDR2") (class "Default")
      (node (ref "RP11") (pin "6") (pinfunction "6_6") (pintype "passive"))
      (node (ref "S1") (pin "2") (pinfunction "A2_2") (pintype "passive"))
      (node (ref "U2") (pin "10") (pinfunction "P1.5/ADC5/SCLK_10") (pintype "passive"))
    )
    (net (code "5") (name "/ADDR3") (class "Default")
      (node (ref "RP11") (pin "7") (pinfunction "7_7") (pintype "passive"))
      (node (ref "S1") (pin "3") (pinfunction "A3_3") (pintype "passive"))
      (node (ref "U2") (pin "9") (pinfunction "P1.4/ADC4/MISO_9") (pintype "passive"))
    )
    (net (code "6") (name "/ADDR4") (class "Default")
      (node (ref "RP11") (pin "8") (pinfunction "8_8") (pintype "passive"))
      (node (ref "S1") (pin "4") (pinfunction "A4_4") (pintype "passive"))
      (node (ref "U2") (pin "8") (pinfunction "P1.3/ADC3/MOSI_8") (pintype "passive"))
    )
    (net (code "7") (name "/B") (class "Default")
      (node (ref "D26") (pin "2") (pinfunction "K_2") (pintype "passive"))
      (node (ref "D28") (pin "2") (pinfunction "K_2") (pintype "passive"))
      (node (ref "P1") (pin "4") (pinfunction "4_4") (pintype "passive"))
      (node (ref "P2") (pin "4") (pinfunction "4_4") (pintype "passive"))
      (node (ref "PTC2") (pin "2") (pinfunction "2_2") (pintype "passive"))
    )
    (net (code "8") (name "/CLK1") (class "Default")
      (node (ref "J1") (pin "4") (pinfunction "3_4") (pintype "passive"))
      (node (ref "P45") (pin "6") (pinfunction "6_6") (pintype "passive"))
      (node (ref "U2") (pin "7") (pinfunction "P1.2/ADC2/SS/ECI_7") (pintype "passive"))
    )
    (net (code "9") (name "/CLK2") (class "Default")
      (node (ref "J2") (pin "4") (pinfunction "3_4") (pintype "passive"))
      (node (ref "P46") (pin "6") (pinfunction "6_6") (pintype "passive"))
      (node (ref "U2") (pin "12") (pinfunction "XTAL1/TxD_3/ADC7/P1.7_12") (pintype "passive"))
    )
    (net (code "10") (name "/DATA1_1") (class "Default")
      (node (ref "J1") (pin "9") (pinfunction "8_9") (pintype "passive"))
      (node (ref "P45") (pin "1") (pinfunction "1_1") (pintype "passive"))
      (node (ref "U2") (pin "44") (pinfunction "P0.4/AD4_44") (pintype "passive"))
    )
    (net (code "11") (name "/DATA1_2") (class "Default")
      (node (ref "J1") (pin "6") (pinfunction "5_6") (pintype "passive"))
      (node (ref "P45") (pin "4") (pinfunction "4_4") (pintype "passive"))
      (node (ref "U2") (pin "3") (pinfunction "P0.7/AD7_3") (pintype "passive"))
    )
    (net (code "12") (name "/DATA2_1") (class "Default")
      (node (ref "J2") (pin "9") (pinfunction "8_9") (pintype "passive"))
      (node (ref "P46") (pin "1") (pinfunction "1_1") (pintype "passive"))
      (node (ref "U2") (pin "21") (pinfunction "INT1/P3.3_21") (pintype "passive"))
    )
    (net (code "13") (name "/DATA2_2") (class "Default")
      (node (ref "J2") (pin "6") (pinfunction "5_6") (pintype "passive"))
      (node (ref "P46") (pin "4") (pinfunction "4_4") (pintype "passive"))
      (node (ref "U2") (pin "15") (pinfunction "P5.5_15") (pintype "passive"))
    )
    (net (code "14") (name "/LC1") (class "Default")
      (node (ref "RP3") (pin "6") (pinfunction "6_6") (pintype "passive"))
      (node (ref "U2") (pin "34") (pinfunction "P2.4/A12/ECI_3/SS_2_34") (pintype "passive"))
    )
    (net (code "15") (name "/LC2") (class "Default")
      (node (ref "RP3") (pin "5") (pinfunction "5_5") (pintype "passive"))
      (node (ref "U2") (pin "35") (pinfunction "P2.5/A13/CCP0_3_35") (pintype "passive"))
    )
    (net (code "16") (name "/LC3") (class "Default")
      (node (ref "RP2") (pin "8") (pinfunction "8_8") (pintype "passive"))
      (node (ref "U2") (pin "36") (pinfunction "P2.6/A14/CCP1_3_36") (pintype "passive"))
    )
    (net (code "17") (name "/LC4") (class "Default")
      (node (ref "RP2") (pin "7") (pinfunction "7_7") (pintype "passive"))
      (node (ref "U2") (pin "37") (pinfunction "P2.7/A15/CCP2_3_37") (pintype "passive"))
    )
    (net (code "18") (name "/LC5") (class "Default")
      (node (ref "RP2") (pin "6") (pinfunction "6_6") (pintype "passive"))
      (node (ref "U2") (pin "38") (pinfunction "P4.5/ALE_38") (pintype "passive"))
    )
    (net (code "19") (name "/LC6") (class "Default")
      (node (ref "RP2") (pin "5") (pinfunction "5_5") (pintype "passive"))
      (node (ref "U2") (pin "39") (pinfunction "P4.6/RxD2_2_39") (pintype "passive"))
    )
    (net (code "20") (name "/LC7") (class "Default")
      (node (ref "RP1") (pin "8") (pinfunction "8_8") (pintype "passive"))
      (node (ref "U2") (pin "40") (pinfunction "P0.0/AD0_40") (pintype "passive"))
    )
    (net (code "21") (name "/LC8") (class "Default")
      (node (ref "RP1") (pin "7") (pinfunction "7_7") (pintype "passive"))
      (node (ref "U2") (pin "41") (pinfunction "P0.1/AD1_41") (pintype "passive"))
    )
    (net (code "22") (name "/LC9") (class "Default")
      (node (ref "RP1") (pin "6") (pinfunction "6_6") (pintype "passive"))
      (node (ref "U2") (pin "42") (pinfunction "P0.2/AD2_42") (pintype "passive"))
    )
    (net (code "23") (name "/LC10") (class "Default")
      (node (ref "RP1") (pin "5") (pinfunction "5_5") (pintype "passive"))
      (node (ref "U2") (pin "43") (pinfunction "P0.3/AD3_43") (pintype "passive"))
    )
    (net (code "24") (name "/LC11") (class "Default")
      (node (ref "RP3") (pin "7") (pinfunction "7_7") (pintype "passive"))
      (node (ref "U2") (pin "33") (pinfunction "MOSI_2/A11/P2.3_33") (pintype "passive"))
    )
    (net (code "25") (name "/LC12") (class "Default")
      (node (ref "RP3") (pin "8") (pinfunction "8_8") (pintype "passive"))
      (node (ref "U2") (pin "32") (pinfunction "MISO_2/A10/P2.2_32") (pintype "passive"))
    )
    (net (code "26") (name "/LC13") (class "Default")
      (node (ref "RP4") (pin "5") (pinfunction "5_5") (pintype "passive"))
      (node (ref "U2") (pin "31") (pinfunction "SCLK_2/A9/P2.1_31") (pintype "passive"))
    )
    (net (code "27") (name "/LC14") (class "Default")
      (node (ref "RP4") (pin "6") (pinfunction "6_6") (pintype "passive"))
      (node (ref "U2") (pin "30") (pinfunction "RSTOUT_LOW/A8/P2.0_30") (pintype "passive"))
    )
    (net (code "28") (name "/LC15") (class "Default")
      (node (ref "RP4") (pin "7") (pinfunction "7_7") (pintype "passive"))
      (node (ref "U2") (pin "29") (pinfunction "~{RD}/P4.4_29") (pintype "passive"))
    )
    (net (code "29") (name "/LC16") (class "Default")
      (node (ref "RP4") (pin "8") (pinfunction "8_8") (pintype "passive"))
      (node (ref "U2") (pin "28") (pinfunction "SCLK_3/P4.3_28") (pintype "passive"))
    )
    (net (code "30") (name "/LC17") (class "Default")
      (node (ref "RP5") (pin "5") (pinfunction "5_5") (pintype "passive"))
      (node (ref "U2") (pin "27") (pinfunction "~{WR}/P4.2_27") (pintype "passive"))
    )
    (net (code "31") (name "/LC18") (class "Default")
      (node (ref "RP5") (pin "6") (pinfunction "6_6") (pintype "passive"))
      (node (ref "U2") (pin "26") (pinfunction "MISO-3/P4.1_26") (pintype "passive"))
    )
    (net (code "32") (name "/LC19") (class "Default")
      (node (ref "RP5") (pin "7") (pinfunction "7_7") (pintype "passive"))
      (node (ref "U2") (pin "25") (pinfunction "CCP2_2/CCP2/TxD_2/~{INT3}/P3.7_25") (pintype "passive"))
    )
    (net (code "33") (name "/LC20") (class "Default")
      (node (ref "RP5") (pin "8") (pinfunction "8_8") (pintype "passive"))
      (node (ref "U2") (pin "24") (pinfunction "CCP1_2/RxD_2/~{INT2}/P3.6_24") (pintype "passive"))
    )
    (net (code "34") (name "/LC_DRV1") (class "Default")
      (node (ref "R3") (pin "1") (pinfunction "1_1") (pintype "passive"))
      (node (ref "U5") (pin "14") (pinfunction "OUT3_14") (pintype "open_collector"))
    )
    (net (code "35") (name "/LC_DRV2") (class "Default")
      (node (ref "R4") (pin "1") (pinfunction "1_1") (pintype "passive"))
      (node (ref "U5") (pin "15") (pinfunction "OUT2_15") (pintype "open_collector"))
    )
    (net (code "36") (name "/LC_DRV3") (class "Default")
      (node (ref "R11") (pin "1") (pinfunction "1_1") (pintype "passive"))
      (node (ref "U5") (pin "16") (pinfunction "OUT1_16") (pintype "open_collector"))
    )
    (net (code "37") (name "/LC_DRV4") (class "Default")
      (node (ref "R12") (pin "1") (pinfunction "1_1") (pintype "passive"))
      (node (ref "U4") (pin "10") (pinfunction "OUT7_10") (pintype "open_collector"))
    )
    (net (code "38") (name "/LC_DRV5") (class "Default")
      (node (ref "R21") (pin "1") (pinfunction "1_1") (pintype "passive"))
      (node (ref "U4") (pin "11") (pinfunction "OUT6_11") (pintype "open_collector"))
    )
    (net (code "39") (name "/LC_DRV6") (class "Default")
      (node (ref "R22") (pin "1") (pinfunction "1_1") (pintype "passive"))
      (node (ref "U4") (pin "12") (pinfunction "OUT5_12") (pintype "open_collector"))
    )
    (net (code "40") (name "/LC_DRV7") (class "Default")
      (node (ref "R27") (pin "1") (pinfunction "1_1") (pintype "passive"))
      (node (ref "U4") (pin "13") (pinfunction "OUT4_13") (pintype "open_collector"))
    )
    (net (code "41") (name "/LC_DRV8") (class "Default")
      (node (ref "R28") (pin "1") (pinfunction "1_1") (pintype "passive"))
      (node (ref "U4") (pin "14") (pinfunction "OUT3_14") (pintype "open_collector"))
    )
    (net (code "42") (name "/LC_DRV9") (class "Default")
      (node (ref "R31") (pin "1") (pinfunction "1_1") (pintype "passive"))
      (node (ref "U4") (pin "15") (pinfunction "OUT2_15") (pintype "open_collector"))
    )
    (net (code "43") (name "/LC_DRV10") (class "Default")
      (node (ref "R32") (pin "1") (pinfunction "1_1") (pintype "passive"))
      (node (ref "U4") (pin "16") (pinfunction "OUT1_16") (pintype "open_collector"))
    )
    (net (code "44") (name "/LC_DRV11") (class "Default")
      (node (ref "R36") (pin "1") (pinfunction "1_1") (pintype "passive"))
      (node (ref "U5") (pin "12") (pinfunction "OUT5_12") (pintype "open_collector"))
    )
    (net (code "45") (name "/LC_DRV12") (class "Default")
      (node (ref "R37") (pin "1") (pinfunction "1_1") (pintype "passive"))
      (node (ref "U5") (pin "11") (pinfunction "OUT6_11") (pintype "open_collector"))
    )
    (net (code "46") (name "/LC_DRV13") (class "Default")
      (node (ref "R40") (pin "1") (pinfunction "1_1") (pintype "passive"))
      (node (ref "U5") (pin "10") (pinfunction "OUT7_10") (pintype "open_collector"))
    )
    (net (code "47") (name "/LC_DRV14") (class "Default")
      (node (ref "R41") (pin "1") (pinfunction "1_1") (pintype "passive"))
      (node (ref "U6") (pin "16") (pinfunction "OUT1_16") (pintype "open_collector"))
    )
    (net (code "48") (name "/LC_DRV15") (class "Default")
      (node (ref "R1") (pin "1") (pinfunction "1_1") (pintype "passive"))
      (node (ref "U6") (pin "15") (pinfunction "OUT2_15") (pintype "open_collector"))
    )
    (net (code "49") (name "/LC_DRV16") (class "Default")
      (node (ref "R2") (pin "1") (pinfunction "1_1") (pintype "passive"))
      (node (ref "U6") (pin "14") (pinfunction "OUT3_14") (pintype "open_collector"))
    )
    (net (code "50") (name "/LC_DRV17") (class "Default")
      (node (ref "R9") (pin "1") (pinfunction "1_1") (pintype "passive"))
      (node (ref "U6") (pin "13") (pinfunction "OUT4_13") (pintype "open_collector"))
    )
    (net (code "51") (name "/LC_DRV18") (class "Default")
      (node (ref "R10") (pin "1") (pinfunction "1_1") (pintype "passive"))
      (node (ref "U6") (pin "12") (pinfunction "OUT5_12") (pintype "open_collector"))
    )
    (net (code "52") (name "/LC_DRV19") (class "Default")
      (node (ref "R17") (pin "1") (pinfunction "1_1") (pintype "passive"))
      (node (ref "U6") (pin "11") (pinfunction "OUT6_11") (pintype "open_collector"))
    )
    (net (code "53") (name "/LC_DRV20") (class "Default")
      (node (ref "R18") (pin "1") (pinfunction "1_1") (pintype "passive"))
      (node (ref "U6") (pin "10") (pinfunction "OUT7_10") (pintype "open_collector"))
    )
    (net (code "54") (name "/LED1") (class "Default")
      (node (ref "D17") (pin "2") (pinfunction "K_2") (pintype "passive"))
      (node (ref "U2") (pin "23") (pinfunction "CCP0_2/T0CLKO/T1/P3.5_23") (pintype "passive"))
    )
    (net (code "55") (name "/RS485") (class "Default")
      (node (ref "R35") (pin "2") (pinfunction "2_2") (pintype "passive"))
      (node (ref "U2") (pin "22") (pinfunction "ECI_2/T1CLKO/T0/P3.4_22") (pintype "passive"))
      (node (ref "U3") (pin "2") (pinfunction "~{RE}_2") (pintype "input"))
      (node (ref "U3") (pin "3") (pinfunction "DE_3") (pintype "input"))
    )
    (net (code "56") (name "/RxD") (class "Default")
      (node (ref "U2") (pin "4") (pinfunction "P1.0/ADC0/CCP1/RxD2_4") (pintype "passive"))
      (node (ref "U3") (pin "1") (pinfunction "RO_1") (pintype "output"))
    )
    (net (code "57") (name "/RxD2") (class "Default")
      (node (ref "P3") (pin "3") (pinfunction "3_3") (pintype "passive"))
      (node (ref "U2") (pin "18") (pinfunction "T2CLKO/~{INT4}/RxD/P3.0_18") (pintype "passive"))
    )
    (net (code "58") (name "/SCLK1") (class "Default")
      (node (ref "J1") (pin "7") (pinfunction "6_7") (pintype "passive"))
      (node (ref "P45") (pin "3") (pinfunction "3_3") (pintype "passive"))
      (node (ref "U2") (pin "2") (pinfunction "P0.6/AD6_2") (pintype "passive"))
    )
    (net (code "59") (name "/SCLK2") (class "Default")
      (node (ref "J2") (pin "7") (pinfunction "6_7") (pintype "passive"))
      (node (ref "P46") (pin "3") (pinfunction "3_3") (pintype "passive"))
      (node (ref "U2") (pin "17") (pinfunction "MOSI_3/P4.0_17") (pintype "passive"))
    )
    (net (code "60") (name "/SL1") (class "Default")
      (node (ref "J1") (pin "8") (pinfunction "7_8") (pintype "passive"))
      (node (ref "P45") (pin "2") (pinfunction "2_2") (pintype "passive"))
      (node (ref "U2") (pin "1") (pinfunction "P0.5/AD5_1") (pintype "passive"))
    )
    (net (code "61") (name "/SL2") (class "Default")
      (node (ref "J2") (pin "8") (pinfunction "7_8") (pintype "passive"))
      (node (ref "P46") (pin "2") (pinfunction "2_2") (pintype "passive"))
      (node (ref "U2") (pin "20") (pinfunction "INT0/P3.2_20") (pintype "passive"))
    )
    (net (code "62") (name "/SRCLK1") (class "Default")
      (node (ref "J1") (pin "5") (pinfunction "4_5") (pintype "passive"))
      (node (ref "P45") (pin "5") (pinfunction "5_5") (pintype "passive"))
      (node (ref "U2") (pin "6") (pinfunction "P4.7/TxD2_2_6") (pintype "passive"))
    )
    (net (code "63") (name "/SRCLK2") (class "Default")
      (node (ref "J2") (pin "5") (pinfunction "4_5") (pintype "passive"))
      (node (ref "P46") (pin "5") (pinfunction "5_5") (pintype "passive"))
      (node (ref "U2") (pin "13") (pinfunction "SS_3/MCLKO/RST/P5.4_13") (pintype "passive"))
    )
    (net (code "64") (name "/TxD") (class "Default")
      (node (ref "U2") (pin "5") (pinfunction "P1.1/ADC1/CCP0/TxD2_5") (pintype "passive"))
      (node (ref "U3") (pin "4") (pinfunction "DI_4") (pintype "input"))
    )
    (net (code "65") (name "/TxD2") (class "Default")
      (node (ref "P3") (pin "2") (pinfunction "2_2") (pintype "passive"))
      (node (ref "U2") (pin "19") (pinfunction "T2/TxD/P3.1_19") (pintype "passive"))
    )
    (net (code "66") (name "GND") (class "Default")
      (node (ref "C1") (pin "1") (pinfunction "1_1") (pintype "passive"))
      (node (ref "C10") (pin "1") (pinfunction "1_1") (pintype "passive"))
      (node (ref "C11") (pin "1") (pinfunction "1_1") (pintype "passive"))
      (node (ref "C12") (pin "1") (pinfunction "1_1") (pintype "passive"))
      (node (ref "C13") (pin "2") (pinfunction "2_2") (pintype "passive"))
      (node (ref "C14") (pin "2") (pinfunction "2_2") (pintype "passive"))
      (node (ref "C15") (pin "1") (pinfunction "1_1") (pintype "passive"))
      (node (ref "C16") (pin "1") (pinfunction "1_1") (pintype "passive"))
      (node (ref "C17") (pin "1") (pinfunction "1_1") (pintype "passive"))
      (node (ref "C18") (pin "1") (pinfunction "1_1") (pintype "passive"))
      (node (ref "C19") (pin "1") (pinfunction "1_1") (pintype "passive"))
      (node (ref "C2") (pin "1") (pinfunction "1_1") (pintype "passive"))
      (node (ref "C20") (pin "1") (pinfunction "1_1") (pintype "passive"))
      (node (ref "C21") (pin "1") (pinfunction "1_1") (pintype "passive"))
      (node (ref "C22") (pin "1") (pinfunction "1_1") (pintype "passive"))
      (node (ref "C23") (pin "2") (pinfunction "2_2") (pintype "passive"))
      (node (ref "C24") (pin "1") (pinfunction "1_1") (pintype "passive"))
      (node (ref "C25") (pin "1") (pinfunction "1_1") (pintype "passive"))
      (node (ref "C26") (pin "1") (pinfunction "1_1") (pintype "passive"))
      (node (ref "C27") (pin "1") (pinfunction "1_1") (pintype "passive"))
      (node (ref "C3") (pin "1") (pinfunction "1_1") (pintype "passive"))
      (node (ref "C4") (pin "1") (pinfunction "1_1") (pintype "passive"))
      (node (ref "C5") (pin "2") (pinfunction "2_2") (pintype "passive"))
      (node (ref "C6") (pin "2") (pinfunction "2_2") (pintype "passive"))
      (node (ref "C7") (pin "2") (pinfunction "2_2") (pintype "passive"))
      (node (ref "C8") (pin "1") (pinfunction "1_1") (pintype "passive"))
      (node (ref "C9") (pin "1") (pinfunction "1_1") (pintype "passive"))
      (node (ref "D1") (pin "1") (pinfunction "A_1") (pintype "passive"))
      (node (ref "D10") (pin "1") (pinfunction "A_1") (pintype "passive"))
      (node (ref "D11") (pin "1") (pinfunction "A_1") (pintype "passive"))
      (node (ref "D12") (pin "1") (pinfunction "A_1") (pintype "passive"))
      (node (ref "D13") (pin "1") (pinfunction "A_1") (pintype "passive"))
      (node (ref "D15") (pin "1") (pinfunction "A_1") (pintype "passive"))
      (node (ref "D16") (pin "1") (pinfunction "A_1") (pintype "passive"))
      (node (ref "D18") (pin "1") (pinfunction "A_1") (pintype "passive"))
      (node (ref "D19") (pin "1") (pinfunction "A_1") (pintype "passive"))
      (node (ref "D2") (pin "1") (pinfunction "A_1") (pintype "passive"))
      (node (ref "D20") (pin "1") (pinfunction "A_1") (pintype "passive"))
      (node (ref "D21") (pin "1") (pinfunction "A_1") (pintype "passive"))
      (node (ref "D22") (pin "1") (pinfunction "A_1") (pintype "passive"))
      (node (ref "D23") (pin "1") (pinfunction "A_1") (pintype "passive"))
      (node (ref "D24") (pin "1") (pinfunction "A_1") (pintype "passive"))
      (node (ref "D25") (pin "1") (pinfunction "A_1") (pintype "passive"))
      (node (ref "D26") (pin "1") (pinfunction "A_1") (pintype "passive"))
      (node (ref "D27") (pin "1") (pinfunction "A_1") (pintype "passive"))
      (node (ref "D29") (pin "1") (pinfunction "C_1") (pintype "passive"))
      (node (ref "D3") (pin "1") (pinfunction "A_1") (pintype "passive"))
      (node (ref "D30") (pin "1") (pinfunction "C_1") (pintype "passive"))
      (node (ref "D4") (pin "1") (pinfunction "A_1") (pintype "passive"))
      (node (ref "D6") (pin "1") (pinfunction "A_1") (pintype "passive"))
      (node (ref "D7") (pin "1") (pinfunction "A_1") (pintype "passive"))
      (node (ref "D9") (pin "1") (pinfunction "A_1") (pintype "passive"))
      (node (ref "P1") (pin "2") (pinfunction "2_2") (pintype "passive"))
      (node (ref "P10") (pin "2") (pinfunction "2_2") (pintype "passive"))
      (node (ref "P11") (pin "2") (pinfunction "2_2") (pintype "passive"))
      (node (ref "P12") (pin "2") (pinfunction "2_2") (pintype "passive"))
      (node (ref "P13") (pin "2") (pinfunction "2_2") (pintype "passive"))
      (node (ref "P14") (pin "2") (pinfunction "2_2") (pintype "passive"))
      (node (ref "P15") (pin "2") (pinfunction "2_2") (pintype "passive"))
      (node (ref "P16") (pin "2") (pinfunction "2_2") (pintype "passive"))
      (node (ref "P17") (pin "2") (pinfunction "2_2") (pintype "passive"))
      (node (ref "P18") (pin "2") (pinfunction "2_2") (pintype "passive"))
      (node (ref "P19") (pin "2") (pinfunction "2_2") (pintype "passive"))
      (node (ref "P2") (pin "2") (pinfunction "2_2") (pintype "passive"))
      (node (ref "P20") (pin "2") (pinfunction "2_2") (pintype "passive"))
      (node (ref "P21") (pin "2") (pinfunction "2_2") (pintype "passive"))
      (node (ref "P22") (pin "2") (pinfunction "2_2") (pintype "passive"))
      (node (ref "P23") (pin "2") (pinfunction "2_2") (pintype "passive"))
      (node (ref "P24") (pin "2") (pinfunction "2_2") (pintype "passive"))
      (node (ref "P26") (pin "2") (pinfunction "2_2") (pintype "passive"))
      (node (ref "P27") (pin "2") (pinfunction "2_2") (pintype "passive"))
      (node (ref "P28") (pin "2") (pinfunction "2_2") (pintype "passive"))
      (node (ref "P29") (pin "2") (pinfunction "2_2") (pintype "passive"))
      (node (ref "P3") (pin "1") (pinfunction "1_1") (pintype "passive"))
      (node (ref "P30") (pin "2") (pinfunction "2_2") (pintype "passive"))
      (node (ref "P31") (pin "2") (pinfunction "2_2") (pintype "passive"))
      (node (ref "P32") (pin "2") (pinfunction "2_2") (pintype "passive"))
      (node (ref "P33") (pin "2") (pinfunction "2_2") (pintype "passive"))
      (node (ref "P34") (pin "2") (pinfunction "2_2") (pintype "passive"))
      (node (ref "P35") (pin "2") (pinfunction "2_2") (pintype "passive"))
      (node (ref "P36") (pin "2") (pinfunction "2_2") (pintype "passive"))
      (node (ref "P37") (pin "2") (pinfunction "2_2") (pintype "passive"))
      (node (ref "P38") (pin "2") (pinfunction "2_2") (pintype "passive"))
      (node (ref "P39") (pin "2") (pinfunction "2_2") (pintype "passive"))
      (node (ref "P4") (pin "2") (pinfunction "2_2") (pintype "passive"))
      (node (ref "P40") (pin "2") (pinfunction "2_2") (pintype "passive"))
      (node (ref "P41") (pin "2") (pinfunction "2_2") (pintype "passive"))
      (node (ref "P42") (pin "2") (pinfunction "2_2") (pintype "passive"))
      (node (ref "P43") (pin "2") (pinfunction "2_2") (pintype "passive"))
      (node (ref "P44") (pin "2") (pinfunction "2_2") (pintype "passive"))
      (node (ref "P45") (pin "7") (pinfunction "7_7") (pintype "passive"))
      (node (ref "P46") (pin "7") (pinfunction "7_7") (pintype "passive"))
      (node (ref "P5") (pin "2") (pinfunction "2_2") (pintype "passive"))
      (node (ref "P6") (pin "2") (pinfunction "2_2") (pintype "passive"))
      (node (ref "P7") (pin "2") (pinfunction "2_2") (pintype "passive"))
      (node (ref "P8") (pin "2") (pinfunction "2_2") (pintype "passive"))
      (node (ref "P9") (pin "2") (pinfunction "2_2") (pintype "passive"))
      (node (ref "R23") (pin "1") (pinfunction "1_1") (pintype "passive"))
      (node (ref "R35") (pin "1") (pinfunction "1_1") (pintype "passive"))
      (node (ref "RP10") (pin "1") (pinfunction "1_1") (pintype "passive"))
      (node (ref "RP10") (pin "2") (pinfunction "2_2") (pintype "passive"))
      (node (ref "RP10") (pin "3") (pinfunction "3_3") (pintype "passive"))
      (node (ref "RP10") (pin "4") (pinfunction "4_4") (pintype "passive"))
      (node (ref "RP6") (pin "1") (pinfunction "1_1") (pintype "passive"))
      (node (ref "RP6") (pin "2") (pinfunction "2_2") (pintype "passive"))
      (node (ref "RP6") (pin "3") (pinfunction "3_3") (pintype "passive"))
      (node (ref "RP6") (pin "4") (pinfunction "4_4") (pintype "passive"))
      (node (ref "RP7") (pin "1") (pinfunction "1_1") (pintype "passive"))
      (node (ref "RP7") (pin "2") (pinfunction "2_2") (pintype "passive"))
      (node (ref "RP7") (pin "3") (pinfunction "3_3") (pintype "passive"))
      (node (ref "RP7") (pin "4") (pinfunction "4_4") (pintype "passive"))
      (node (ref "RP8") (pin "1") (pinfunction "1_1") (pintype "passive"))
      (node (ref "RP8") (pin "2") (pinfunction "2_2") (pintype "passive"))
      (node (ref "RP8") (pin "3") (pinfunction "3_3") (pintype "passive"))
      (node (ref "RP8") (pin "4") (pinfunction "4_4") (pintype "passive"))
      (node (ref "RP9") (pin "1") (pinfunction "1_1") (pintype "passive"))
      (node (ref "RP9") (pin "2") (pinfunction "2_2") (pintype "passive"))
      (node (ref "RP9") (pin "3") (pinfunction "3_3") (pintype "passive"))
      (node (ref "RP9") (pin "4") (pinfunction "4_4") (pintype "passive"))
      (node (ref "S1") (pin "5") (pinfunction "B4_5") (pintype "passive"))
      (node (ref "S1") (pin "6") (pinfunction "B3_6") (pintype "passive"))
      (node (ref "S1") (pin "7") (pinfunction "B2_7") (pintype "passive"))
      (node (ref "S1") (pin "8") (pinfunction "B1_8") (pintype "passive"))
      (node (ref "U1") (pin "2") (pinfunction "GND_2") (pintype "passive"))
      (node (ref "U1") (pin "4") (pinfunction "GND_4") (pintype "passive"))
      (node (ref "U2") (pin "16") (pinfunction "GND_16") (pintype "power_in"))
      (node (ref "U3") (pin "5") (pinfunction "GND_5") (pintype "power_in"))
      (node (ref "U4") (pin "8") (pinfunction "GND_8") (pintype "power_in"))
      (node (ref "U5") (pin "8") (pinfunction "GND_8") (pintype "power_in"))
      (node (ref "U6") (pin "8") (pinfunction "GND_8") (pintype "power_in"))
    )
    (net (code "67") (name "Net-(D1-K)") (class "Default")
      (node (ref "C1") (pin "2") (pinfunction "2_2") (pintype "passive"))
      (node (ref "D1") (pin "2") (pinfunction "K_2") (pintype "passive"))
      (node (ref "P10") (pin "1") (pinfunction "1_1") (pintype "passive"))
      (node (ref "P4") (pin "1") (pinfunction "1_1") (pintype "passive"))
      (node (ref "Q1") (pin "7") (pinfunction "D_7") (pintype "passive"))
      (node (ref "Q1") (pin "8") (pinfunction "D_8") (pintype "passive"))
    )
    (net (code "68") (name "Net-(D2-K)") (class "Default")
      (node (ref "C2") (pin "2") (pinfunction "2_2") (pintype "passive"))
      (node (ref "D2") (pin "2") (pinfunction "K_2") (pintype "passive"))
      (node (ref "P11") (pin "1") (pinfunction "1_1") (pintype "passive"))
      (node (ref "P5") (pin "1") (pinfunction "1_1") (pintype "passive"))
      (node (ref "Q1") (pin "5") (pinfunction "D_5") (pintype "passive"))
      (node (ref "Q1") (pin "6") (pinfunction "D_6") (pintype "passive"))
    )
    (net (code "69") (name "Net-(D3-K)") (class "Default")
      (node (ref "C3") (pin "2") (pinfunction "2_2") (pintype "passive"))
      (node (ref "D3") (pin "2") (pinfunction "K_2") (pintype "passive"))
      (node (ref "P6") (pin "1") (pinfunction "1_1") (pintype "passive"))
      (node (ref "P8") (pin "1") (pinfunction "1_1") (pintype "passive"))
      (node (ref "Q2") (pin "7") (pinfunction "D_7") (pintype "passive"))
      (node (ref "Q2") (pin "8") (pinfunction "D_8") (pintype "passive"))
    )
    (net (code "70") (name "Net-(D4-K)") (class "Default")
      (node (ref "C4") (pin "2") (pinfunction "2_2") (pintype "passive"))
      (node (ref "D4") (pin "2") (pinfunction "K_2") (pintype "passive"))
      (node (ref "P7") (pin "1") (pinfunction "1_1") (pintype "passive"))
      (node (ref "P9") (pin "1") (pinfunction "1_1") (pintype "passive"))
      (node (ref "Q2") (pin "5") (pinfunction "D_5") (pintype "passive"))
      (node (ref "Q2") (pin "6") (pinfunction "D_6") (pintype "passive"))
    )
    (net (code "71") (name "Net-(D5-K)") (class "Default")
      (node (ref "C7") (pin "1") (pinfunction "1_1") (pintype "passive"))
      (node (ref "C8") (pin "2") (pinfunction "2_2") (pintype "passive"))
      (node (ref "D5") (pin "2") (pinfunction "K_2") (pintype "passive"))
      (node (ref "D8") (pin "2") (pinfunction "K_2") (pintype "passive"))
      (node (ref "U1") (pin "1") (pinfunction "IN_1") (pintype "passive"))
    )
    (net (code "72") (name "Net-(D6-K)") (class "Default")
      (node (ref "C9") (pin "2") (pinfunction "2_2") (pintype "passive"))
      (node (ref "D6") (pin "2") (pinfunction "K_2") (pintype "passive"))
      (node (ref "P12") (pin "1") (pinfunction "1_1") (pintype "passive"))
      (node (ref "P16") (pin "1") (pinfunction "1_1") (pintype "passive"))
      (node (ref "Q3") (pin "7") (pinfunction "D_7") (pintype "passive"))
      (node (ref "Q3") (pin "8") (pinfunction "D_8") (pintype "passive"))
    )
    (net (code "73") (name "Net-(D7-K)") (class "Default")
      (node (ref "C10") (pin "2") (pinfunction "2_2") (pintype "passive"))
      (node (ref "D7") (pin "2") (pinfunction "K_2") (pintype "passive"))
      (node (ref "P13") (pin "1") (pinfunction "1_1") (pintype "passive"))
      (node (ref "P17") (pin "1") (pinfunction "1_1") (pintype "passive"))
      (node (ref "Q3") (pin "5") (pinfunction "D_5") (pintype "passive"))
      (node (ref "Q3") (pin "6") (pinfunction "D_6") (pintype "passive"))
    )
    (net (code "74") (name "Net-(D9-K)") (class "Default")
      (node (ref "C11") (pin "2") (pinfunction "2_2") (pintype "passive"))
      (node (ref "D9") (pin "2") (pinfunction "K_2") (pintype "passive"))
      (node (ref "P14") (pin "1") (pinfunction "1_1") (pintype "passive"))
      (node (ref "P18") (pin "1") (pinfunction "1_1") (pintype "passive"))
      (node (ref "Q4") (pin "7") (pinfunction "D_7") (pintype "passive"))
      (node (ref "Q4") (pin "8") (pinfunction "D_8") (pintype "passive"))
    )
    (net (code "75") (name "Net-(D10-K)") (class "Default")
      (node (ref "C12") (pin "2") (pinfunction "2_2") (pintype "passive"))
      (node (ref "D10") (pin "2") (pinfunction "K_2") (pintype "passive"))
      (node (ref "P15") (pin "1") (pinfunction "1_1") (pintype "passive"))
      (node (ref "P19") (pin "1") (pinfunction "1_1") (pintype "passive"))
      (node (ref "Q4") (pin "5") (pinfunction "D_5") (pintype "passive"))
      (node (ref "Q4") (pin "6") (pinfunction "D_6") (pintype "passive"))
    )
    (net (code "76") (name "Net-(D11-K)") (class "Default")
      (node (ref "C15") (pin "2") (pinfunction "2_2") (pintype "passive"))
      (node (ref "D11") (pin "2") (pinfunction "K_2") (pintype "passive"))
      (node (ref "P20") (pin "1") (pinfunction "1_1") (pintype "passive"))
      (node (ref "P22") (pin "1") (pinfunction "1_1") (pintype "passive"))
      (node (ref "Q5") (pin "7") (pinfunction "D_7") (pintype "passive"))
      (node (ref "Q5") (pin "8") (pinfunction "D_8") (pintype "passive"))
    )
    (net (code "77") (name "Net-(D12-K)") (class "Default")
      (node (ref "C16") (pin "2") (pinfunction "2_2") (pintype "passive"))
      (node (ref "D12") (pin "2") (pinfunction "K_2") (pintype "passive"))
      (node (ref "P21") (pin "1") (pinfunction "1_1") (pintype "passive"))
      (node (ref "P23") (pin "1") (pinfunction "1_1") (pintype "passive"))
      (node (ref "Q5") (pin "5") (pinfunction "D_5") (pintype "passive"))
      (node (ref "Q5") (pin "6") (pinfunction "D_6") (pintype "passive"))
    )
    (net (code "78") (name "Net-(D14-K)") (class "Default")
      (node (ref "D14") (pin "2") (pinfunction "K_2") (pintype "passive"))
      (node (ref "R23") (pin "2") (pinfunction "2_2") (pintype "passive"))
    )
    (net (code "79") (name "Net-(D15-K)") (class "Default")
      (node (ref "C17") (pin "2") (pinfunction "2_2") (pintype "passive"))
      (node (ref "D15") (pin "2") (pinfunction "K_2") (pintype "passive"))
      (node (ref "P24") (pin "1") (pinfunction "1_1") (pintype "passive"))
      (node (ref "P26") (pin "1") (pinfunction "1_1") (pintype "passive"))
      (node (ref "Q6") (pin "7") (pinfunction "D_7") (pintype "passive"))
      (node (ref "Q6") (pin "8") (pinfunction "D_8") (pintype "passive"))
    )
    (net (code "80") (name "Net-(D16-K)") (class "Default")
      (node (ref "C18") (pin "2") (pinfunction "2_2") (pintype "passive"))
      (node (ref "D16") (pin "2") (pinfunction "K_2") (pintype "passive"))
      (node (ref "P27") (pin "1") (pinfunction "1_1") (pintype "passive"))
      (node (ref "P28") (pin "1") (pinfunction "1_1") (pintype "passive"))
      (node (ref "Q6") (pin "5") (pinfunction "D_5") (pintype "passive"))
      (node (ref "Q6") (pin "6") (pinfunction "D_6") (pintype "passive"))
    )
    (net (code "81") (name "Net-(D17-A)") (class "Default")
      (node (ref "D17") (pin "1") (pinfunction "A_1") (pintype "passive"))
      (node (ref "R26") (pin "1") (pinfunction "1_1") (pintype "passive"))
    )
    (net (code "82") (name "Net-(D18-K)") (class "Default")
      (node (ref "C19") (pin "2") (pinfunction "2_2") (pintype "passive"))
      (node (ref "D18") (pin "2") (pinfunction "K_2") (pintype "passive"))
      (node (ref "P29") (pin "1") (pinfunction "1_1") (pintype "passive"))
      (node (ref "P31") (pin "1") (pinfunction "1_1") (pintype "passive"))
      (node (ref "Q7") (pin "7") (pinfunction "D_7") (pintype "passive"))
      (node (ref "Q7") (pin "8") (pinfunction "D_8") (pintype "passive"))
    )
    (net (code "83") (name "Net-(D19-K)") (class "Default")
      (node (ref "C20") (pin "2") (pinfunction "2_2") (pintype "passive"))
      (node (ref "D19") (pin "2") (pinfunction "K_2") (pintype "passive"))
      (node (ref "P30") (pin "1") (pinfunction "1_1") (pintype "passive"))
      (node (ref "P32") (pin "1") (pinfunction "1_1") (pintype "passive"))
      (node (ref "Q7") (pin "5") (pinfunction "D_5") (pintype "passive"))
      (node (ref "Q7") (pin "6") (pinfunction "D_6") (pintype "passive"))
    )
    (net (code "84") (name "Net-(D20-K)") (class "Default")
      (node (ref "C21") (pin "2") (pinfunction "2_2") (pintype "passive"))
      (node (ref "D20") (pin "2") (pinfunction "K_2") (pintype "passive"))
      (node (ref "P34") (pin "1") (pinfunction "1_1") (pintype "passive"))
      (node (ref "P36") (pin "1") (pinfunction "1_1") (pintype "passive"))
      (node (ref "Q8") (pin "7") (pinfunction "D_7") (pintype "passive"))
      (node (ref "Q8") (pin "8") (pinfunction "D_8") (pintype "passive"))
    )
    (net (code "85") (name "Net-(D21-K)") (class "Default")
      (node (ref "C22") (pin "2") (pinfunction "2_2") (pintype "passive"))
      (node (ref "D21") (pin "2") (pinfunction "K_2") (pintype "passive"))
      (node (ref "P35") (pin "1") (pinfunction "1_1") (pintype "passive"))
      (node (ref "P37") (pin "1") (pinfunction "1_1") (pintype "passive"))
      (node (ref "Q8") (pin "5") (pinfunction "D_5") (pintype "passive"))
      (node (ref "Q8") (pin "6") (pinfunction "D_6") (pintype "passive"))
    )
    (net (code "86") (name "Net-(D22-K)") (class "Default")
      (node (ref "C24") (pin "2") (pinfunction "2_2") (pintype "passive"))
      (node (ref "D22") (pin "2") (pinfunction "K_2") (pintype "passive"))
      (node (ref "P38") (pin "1") (pinfunction "1_1") (pintype "passive"))
      (node (ref "P40") (pin "1") (pinfunction "1_1") (pintype "passive"))
      (node (ref "Q11") (pin "7") (pinfunction "D_7") (pintype "passive"))
      (node (ref "Q11") (pin "8") (pinfunction "D_8") (pintype "passive"))
    )
    (net (code "87") (name "Net-(D23-K)") (class "Default")
      (node (ref "C25") (pin "2") (pinfunction "2_2") (pintype "passive"))
      (node (ref "D23") (pin "2") (pinfunction "K_2") (pintype "passive"))
      (node (ref "P39") (pin "1") (pinfunction "1_1") (pintype "passive"))
      (node (ref "P41") (pin "1") (pinfunction "1_1") (pintype "passive"))
      (node (ref "Q11") (pin "5") (pinfunction "D_5") (pintype "passive"))
      (node (ref "Q11") (pin "6") (pinfunction "D_6") (pintype "passive"))
    )
    (net (code "88") (name "Net-(D24-K)") (class "Default")
      (node (ref "C26") (pin "2") (pinfunction "2_2") (pintype "passive"))
      (node (ref "D24") (pin "2") (pinfunction "K_2") (pintype "passive"))
      (node (ref "P42") (pin "1") (pinfunction "1_1") (pintype "passive"))
      (node (ref "P44") (pin "1") (pinfunction "1_1") (pintype "passive"))
      (node (ref "Q12") (pin "7") (pinfunction "D_7") (pintype "passive"))
      (node (ref "Q12") (pin "8") (pinfunction "D_8") (pintype "passive"))
    )
    (net (code "89") (name "Net-(D25-K)") (class "Default")
      (node (ref "C27") (pin "2") (pinfunction "2_2") (pintype "passive"))
      (node (ref "D25") (pin "2") (pinfunction "K_2") (pintype "passive"))
      (node (ref "P33") (pin "1") (pinfunction "1_1") (pintype "passive"))
      (node (ref "P43") (pin "1") (pinfunction "1_1") (pintype "passive"))
      (node (ref "Q12") (pin "5") (pinfunction "D_5") (pintype "passive"))
      (node (ref "Q12") (pin "6") (pinfunction "D_6") (pintype "passive"))
    )
    (net (code "90") (name "Net-(D29-B)") (class "Default")
      (node (ref "D29") (pin "3") (pinfunction "B_3") (pintype "passive"))
      (node (ref "PTC1") (pin "1") (pinfunction "1_1") (pintype "passive"))
      (node (ref "U3") (pin "6") (pinfunction "A_6") (pintype "bidirectional"))
    )
    (net (code "91") (name "Net-(D30-B)") (class "Default")
      (node (ref "D30") (pin "3") (pinfunction "B_3") (pintype "passive"))
      (node (ref "PTC2") (pin "1") (pinfunction "1_1") (pintype "passive"))
      (node (ref "U3") (pin "7") (pinfunction "B_7") (pintype "bidirectional"))
    )
    (net (code "92") (name "Net-(Q1A-G)") (class "Default")
      (node (ref "Q1") (pin "2") (pinfunction "G_2") (pintype "passive"))
      (node (ref "R3") (pin "2") (pinfunction "2_2") (pintype "passive"))
      (node (ref "R5") (pin "1") (pinfunction "1_1") (pintype "passive"))
    )
    (net (code "93") (name "Net-(Q1B-G)") (class "Default")
      (node (ref "Q1") (pin "4") (pinfunction "G_4") (pintype "passive"))
      (node (ref "R4") (pin "2") (pinfunction "2_2") (pintype "passive"))
      (node (ref "R6") (pin "1") (pinfunction "1_1") (pintype "passive"))
    )
    (net (code "94") (name "Net-(Q2A-G)") (class "Default")
      (node (ref "Q2") (pin "2") (pinfunction "G_2") (pintype "passive"))
      (node (ref "R1") (pin "2") (pinfunction "2_2") (pintype "passive"))
      (node (ref "R7") (pin "1") (pinfunction "1_1") (pintype "passive"))
    )
    (net (code "95") (name "Net-(Q2B-G)") (class "Default")
      (node (ref "Q2") (pin "4") (pinfunction "G_4") (pintype "passive"))
      (node (ref "R2") (pin "2") (pinfunction "2_2") (pintype "passive"))
      (node (ref "R8") (pin "1") (pinfunction "1_1") (pintype "passive"))
    )
    (net (code "96") (name "Net-(Q3A-G)") (class "Default")
      (node (ref "Q3") (pin "2") (pinfunction "G_2") (pintype "passive"))
      (node (ref "R13") (pin "1") (pinfunction "1_1") (pintype "passive"))
      (node (ref "R9") (pin "2") (pinfunction "2_2") (pintype "passive"))
    )
    (net (code "97") (name "Net-(Q3B-G)") (class "Default")
      (node (ref "Q3") (pin "4") (pinfunction "G_4") (pintype "passive"))
      (node (ref "R10") (pin "2") (pinfunction "2_2") (pintype "passive"))
      (node (ref "R14") (pin "1") (pinfunction "1_1") (pintype "passive"))
    )
    (net (code "98") (name "Net-(Q4A-G)") (class "Default")
      (node (ref "Q4") (pin "2") (pinfunction "G_2") (pintype "passive"))
      (node (ref "R11") (pin "2") (pinfunction "2_2") (pintype "passive"))
      (node (ref "R15") (pin "1") (pinfunction "1_1") (pintype "passive"))
    )
    (net (code "99") (name "Net-(Q4B-G)") (class "Default")
      (node (ref "Q4") (pin "4") (pinfunction "G_4") (pintype "passive"))
      (node (ref "R12") (pin "2") (pinfunction "2_2") (pintype "passive"))
      (node (ref "R16") (pin "1") (pinfunction "1_1") (pintype "passive"))
    )
    (net (code "100") (name "Net-(Q5A-G)") (class "Default")
      (node (ref "Q5") (pin "2") (pinfunction "G_2") (pintype "passive"))
      (node (ref "R17") (pin "2") (pinfunction "2_2") (pintype "passive"))
      (node (ref "R19") (pin "1") (pinfunction "1_1") (pintype "passive"))
    )
    (net (code "101") (name "Net-(Q5B-G)") (class "Default")
      (node (ref "Q5") (pin "4") (pinfunction "G_4") (pintype "passive"))
      (node (ref "R18") (pin "2") (pinfunction "2_2") (pintype "passive"))
      (node (ref "R20") (pin "1") (pinfunction "1_1") (pintype "passive"))
    )
    (net (code "102") (name "Net-(Q6A-G)") (class "Default")
      (node (ref "Q6") (pin "2") (pinfunction "G_2") (pintype "passive"))
      (node (ref "R21") (pin "2") (pinfunction "2_2") (pintype "passive"))
      (node (ref "R24") (pin "1") (pinfunction "1_1") (pintype "passive"))
    )
    (net (code "103") (name "Net-(Q6B-G)") (class "Default")
      (node (ref "Q6") (pin "4") (pinfunction "G_4") (pintype "passive"))
      (node (ref "R22") (pin "2") (pinfunction "2_2") (pintype "passive"))
      (node (ref "R25") (pin "1") (pinfunction "1_1") (pintype "passive"))
    )
    (net (code "104") (name "Net-(Q7A-G)") (class "Default")
      (node (ref "Q7") (pin "2") (pinfunction "G_2") (pintype "passive"))
      (node (ref "R27") (pin "2") (pinfunction "2_2") (pintype "passive"))
      (node (ref "R29") (pin "1") (pinfunction "1_1") (pintype "passive"))
    )
    (net (code "105") (name "Net-(Q7B-G)") (class "Default")
      (node (ref "Q7") (pin "4") (pinfunction "G_4") (pintype "passive"))
      (node (ref "R28") (pin "2") (pinfunction "2_2") (pintype "passive"))
      (node (ref "R30") (pin "1") (pinfunction "1_1") (pintype "passive"))
    )
    (net (code "106") (name "Net-(Q8A-G)") (class "Default")
      (node (ref "Q8") (pin "2") (pinfunction "G_2") (pintype "passive"))
      (node (ref "R31") (pin "2") (pinfunction "2_2") (pintype "passive"))
      (node (ref "R33") (pin "1") (pinfunction "1_1") (pintype "passive"))
    )
    (net (code "107") (name "Net-(Q8B-G)") (class "Default")
      (node (ref "Q8") (pin "4") (pinfunction "G_4") (pintype "passive"))
      (node (ref "R32") (pin "2") (pinfunction "2_2") (pintype "passive"))
      (node (ref "R34") (pin "1") (pinfunction "1_1") (pintype "passive"))
    )
    (net (code "108") (name "Net-(Q11A-G)") (class "Default")
      (node (ref "Q11") (pin "2") (pinfunction "G_2") (pintype "passive"))
      (node (ref "R36") (pin "2") (pinfunction "2_2") (pintype "passive"))
      (node (ref "R38") (pin "1") (pinfunction "1_1") (pintype "passive"))
    )
    (net (code "109") (name "Net-(Q11B-G)") (class "Default")
      (node (ref "Q11") (pin "4") (pinfunction "G_4") (pintype "passive"))
      (node (ref "R37") (pin "2") (pinfunction "2_2") (pintype "passive"))
      (node (ref "R39") (pin "1") (pinfunction "1_1") (pintype "passive"))
    )
    (net (code "110") (name "Net-(Q12A-G)") (class "Default")
      (node (ref "Q12") (pin "2") (pinfunction "G_2") (pintype "passive"))
      (node (ref "R40") (pin "2") (pinfunction "2_2") (pintype "passive"))
      (node (ref "R42") (pin "1") (pinfunction "1_1") (pintype "passive"))
    )
    (net (code "111") (name "Net-(Q12B-G)") (class "Default")
      (node (ref "Q12") (pin "4") (pinfunction "G_4") (pintype "passive"))
      (node (ref "R41") (pin "2") (pinfunction "2_2") (pintype "passive"))
      (node (ref "R43") (pin "1") (pinfunction "1_1") (pintype "passive"))
    )
    (net (code "112") (name "Net-(U4-IN1)") (class "Default")
      (node (ref "RP1") (pin "4") (pinfunction "4_4") (pintype "passive"))
      (node (ref "RP9") (pin "5") (pinfunction "5_5") (pintype "passive"))
      (node (ref "U4") (pin "1") (pinfunction "IN1_1") (pintype "input"))
    )
    (net (code "113") (name "Net-(U4-IN2)") (class "Default")
      (node (ref "RP1") (pin "3") (pinfunction "3_3") (pintype "passive"))
      (node (ref "RP9") (pin "6") (pinfunction "6_6") (pintype "passive"))
      (node (ref "U4") (pin "2") (pinfunction "IN2_2") (pintype "input"))
    )
    (net (code "114") (name "Net-(U4-IN3)") (class "Default")
      (node (ref "RP1") (pin "2") (pinfunction "2_2") (pintype "passive"))
      (node (ref "RP9") (pin "7") (pinfunction "7_7") (pintype "passive"))
      (node (ref "U4") (pin "3") (pinfunction "IN3_3") (pintype "input"))
    )
    (net (code "115") (name "Net-(U4-IN4)") (class "Default")
      (node (ref "RP1") (pin "1") (pinfunction "1_1") (pintype "passive"))
      (node (ref "RP9") (pin "8") (pinfunction "8_8") (pintype "passive"))
      (node (ref "U4") (pin "4") (pinfunction "IN4_4") (pintype "input"))
    )
    (net (code "116") (name "Net-(U4-IN5)") (class "Default")
      (node (ref "RP2") (pin "4") (pinfunction "4_4") (pintype "passive"))
      (node (ref "RP7") (pin "5") (pinfunction "5_5") (pintype "passive"))
      (node (ref "U4") (pin "5") (pinfunction "IN5_5") (pintype "input"))
    )
    (net (code "117") (name "Net-(U4-IN6)") (class "Default")
      (node (ref "RP2") (pin "3") (pinfunction "3_3") (pintype "passive"))
      (node (ref "RP7") (pin "6") (pinfunction "6_6") (pintype "passive"))
      (node (ref "U4") (pin "6") (pinfunction "IN6_6") (pintype "input"))
    )
    (net (code "118") (name "Net-(U4-IN7)") (class "Default")
      (node (ref "RP2") (pin "2") (pinfunction "2_2") (pintype "passive"))
      (node (ref "RP7") (pin "7") (pinfunction "7_7") (pintype "passive"))
      (node (ref "U4") (pin "7") (pinfunction "IN7_7") (pintype "input"))
    )
    (net (code "119") (name "Net-(U5-IN1)") (class "Default")
      (node (ref "RP2") (pin "1") (pinfunction "1_1") (pintype "passive"))
      (node (ref "RP7") (pin "8") (pinfunction "8_8") (pintype "passive"))
      (node (ref "U5") (pin "1") (pinfunction "IN1_1") (pintype "input"))
    )
    (net (code "120") (name "Net-(U5-IN2)") (class "Default")
      (node (ref "RP10") (pin "5") (pinfunction "5_5") (pintype "passive"))
      (node (ref "RP3") (pin "4") (pinfunction "4_4") (pintype "passive"))
      (node (ref "U5") (pin "2") (pinfunction "IN2_2") (pintype "input"))
    )
    (net (code "121") (name "Net-(U5-IN3)") (class "Default")
      (node (ref "RP10") (pin "6") (pinfunction "6_6") (pintype "passive"))
      (node (ref "RP3") (pin "3") (pinfunction "3_3") (pintype "passive"))
      (node (ref "U5") (pin "3") (pinfunction "IN3_3") (pintype "input"))
    )
    (net (code "122") (name "Net-(U5-IN5)") (class "Default")
      (node (ref "RP10") (pin "7") (pinfunction "7_7") (pintype "passive"))
      (node (ref "RP3") (pin "2") (pinfunction "2_2") (pintype "passive"))
      (node (ref "U5") (pin "5") (pinfunction "IN5_5") (pintype "input"))
    )
    (net (code "123") (name "Net-(U5-IN6)") (class "Default")
      (node (ref "RP10") (pin "8") (pinfunction "8_8") (pintype "passive"))
      (node (ref "RP3") (pin "1") (pinfunction "1_1") (pintype "passive"))
      (node (ref "U5") (pin "6") (pinfunction "IN6_6") (pintype "input"))
    )
    (net (code "124") (name "Net-(U5-IN7)") (class "Default")
      (node (ref "RP4") (pin "4") (pinfunction "4_4") (pintype "passive"))
      (node (ref "RP8") (pin "5") (pinfunction "5_5") (pintype "passive"))
      (node (ref "U5") (pin "7") (pinfunction "IN7_7") (pintype "input"))
    )
    (net (code "125") (name "Net-(U6-IN1)") (class "Default")
      (node (ref "RP4") (pin "3") (pinfunction "3_3") (pintype "passive"))
      (node (ref "RP8") (pin "6") (pinfunction "6_6") (pintype "passive"))
      (node (ref "U6") (pin "1") (pinfunction "IN1_1") (pintype "input"))
    )
    (net (code "126") (name "Net-(U6-IN2)") (class "Default")
      (node (ref "RP4") (pin "2") (pinfunction "2_2") (pintype "passive"))
      (node (ref "RP8") (pin "7") (pinfunction "7_7") (pintype "passive"))
      (node (ref "U6") (pin "2") (pinfunction "IN2_2") (pintype "input"))
    )
    (net (code "127") (name "Net-(U6-IN3)") (class "Default")
      (node (ref "RP4") (pin "1") (pinfunction "1_1") (pintype "passive"))
      (node (ref "RP8") (pin "8") (pinfunction "8_8") (pintype "passive"))
      (node (ref "U6") (pin "3") (pinfunction "IN3_3") (pintype "input"))
    )
    (net (code "128") (name "Net-(U6-IN4)") (class "Default")
      (node (ref "RP5") (pin "4") (pinfunction "4_4") (pintype "passive"))
      (node (ref "RP6") (pin "5") (pinfunction "5_5") (pintype "passive"))
      (node (ref "U6") (pin "4") (pinfunction "IN4_4") (pintype "input"))
    )
    (net (code "129") (name "Net-(U6-IN5)") (class "Default")
      (node (ref "RP5") (pin "3") (pinfunction "3_3") (pintype "passive"))
      (node (ref "RP6") (pin "6") (pinfunction "6_6") (pintype "passive"))
      (node (ref "U6") (pin "5") (pinfunction "IN5_5") (pintype "input"))
    )
    (net (code "130") (name "Net-(U6-IN6)") (class "Default")
      (node (ref "RP5") (pin "2") (pinfunction "2_2") (pintype "passive"))
      (node (ref "RP6") (pin "7") (pinfunction "7_7") (pintype "passive"))
      (node (ref "U6") (pin "6") (pinfunction "IN6_6") (pintype "input"))
    )
    (net (code "131") (name "Net-(U6-IN7)") (class "Default")
      (node (ref "RP5") (pin "1") (pinfunction "1_1") (pintype "passive"))
      (node (ref "RP6") (pin "8") (pinfunction "8_8") (pintype "passive"))
      (node (ref "U6") (pin "7") (pinfunction "IN7_7") (pintype "input"))
    )
    (net (code "132") (name "VCC") (class "Default")
      (node (ref "C13") (pin "1") (pinfunction "1_1") (pintype "passive"))
      (node (ref "C14") (pin "1") (pinfunction "1_1") (pintype "passive"))
      (node (ref "C23") (pin "1") (pinfunction "1_1") (pintype "passive"))
      (node (ref "D13") (pin "2") (pinfunction "K_2") (pintype "passive"))
      (node (ref "D14") (pin "1") (pinfunction "A_1") (pintype "passive"))
      (node (ref "D29") (pin "2") (pinfunction "E_2") (pintype "passive"))
      (node (ref "D30") (pin "2") (pinfunction "E_2") (pintype "passive"))
      (node (ref "D8") (pin "1") (pinfunction "A_1") (pintype "passive"))
      (node (ref "J1") (pin "1") (pinfunction "COM_1") (pintype "passive"))
      (node (ref "J2") (pin "1") (pinfunction "COM_1") (pintype "passive"))
      (node (ref "P3") (pin "4") (pinfunction "4_4") (pintype "passive"))
      (node (ref "P45") (pin "8") (pinfunction "8_8") (pintype "passive"))
      (node (ref "P46") (pin "8") (pinfunction "8_8") (pintype "passive"))
      (node (ref "R26") (pin "2") (pinfunction "2_2") (pintype "passive"))
      (node (ref "RP11") (pin "1") (pinfunction "1_1") (pintype "passive"))
      (node (ref "RP11") (pin "2") (pinfunction "2_2") (pintype "passive"))
      (node (ref "RP11") (pin "3") (pinfunction "3_3") (pintype "passive"))
      (node (ref "RP11") (pin "4") (pinfunction "4_4") (pintype "passive"))
      (node (ref "U1") (pin "3") (pinfunction "OUT_3") (pintype "passive"))
      (node (ref "U2") (pin "14") (pinfunction "VCC_14") (pintype "power_in"))
      (node (ref "U3") (pin "8") (pinfunction "VCC_8") (pintype "power_in"))
    )
    (net (code "133") (name "unconnected-(J1-1-Pad2)") (class "Default")
      (node (ref "J1") (pin "2") (pinfunction "1_2") (pintype "passive+no_connect"))
    )
    (net (code "134") (name "unconnected-(J1-2-Pad3)") (class "Default")
      (node (ref "J1") (pin "3") (pinfunction "2_3") (pintype "passive+no_connect"))
    )
    (net (code "135") (name "unconnected-(J2-1-Pad2)") (class "Default")
      (node (ref "J2") (pin "2") (pinfunction "1_2") (pintype "passive+no_connect"))
    )
    (net (code "136") (name "unconnected-(J2-2-Pad3)") (class "Default")
      (node (ref "J2") (pin "3") (pinfunction "2_3") (pintype "passive+no_connect"))
    )
    (net (code "137") (name "unconnected-(U4-COM-Pad9)") (class "Default")
      (node (ref "U4") (pin "9") (pinfunction "COM_9") (pintype "passive+no_connect"))
    )
    (net (code "138") (name "unconnected-(U5-COM-Pad9)") (class "Default")
      (node (ref "U5") (pin "9") (pinfunction "COM_9") (pintype "passive+no_connect"))
    )
    (net (code "139") (name "unconnected-(U5-IN4-Pad4)") (class "Default")
      (node (ref "U5") (pin "4") (pinfunction "IN4_4") (pintype "input+no_connect"))
    )
    (net (code "140") (name "unconnected-(U5-OUT4-Pad13)") (class "Default")
      (node (ref "U5") (pin "13") (pinfunction "OUT4_13") (pintype "open_collector+no_connect"))
    )
    (net (code "141") (name "unconnected-(U6-COM-Pad9)") (class "Default")
      (node (ref "U6") (pin "9") (pinfunction "COM_9") (pintype "passive+no_connect"))
    )
  )
)
